# AiwacA33.net
KiCad netlist of a schematic drawn in Altium Designer
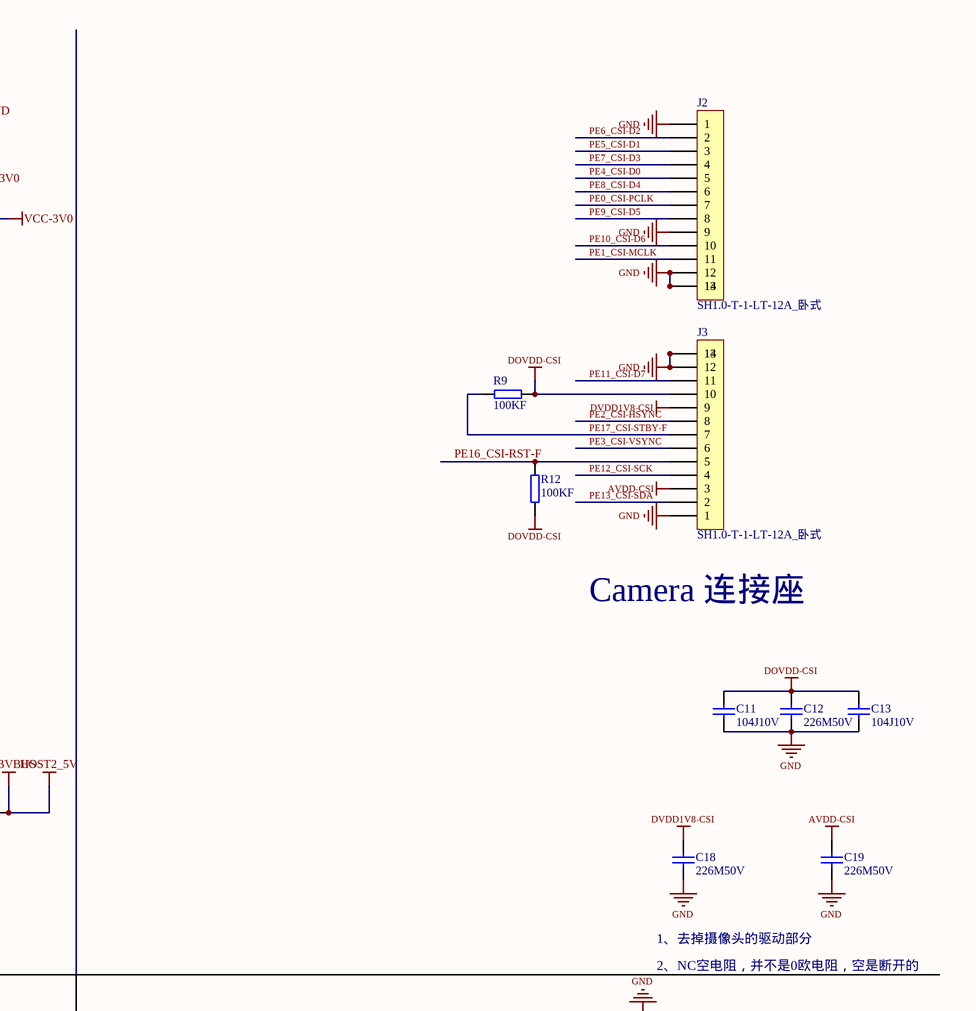
[diagram p0: AiwacA33.SchDoc, top right]
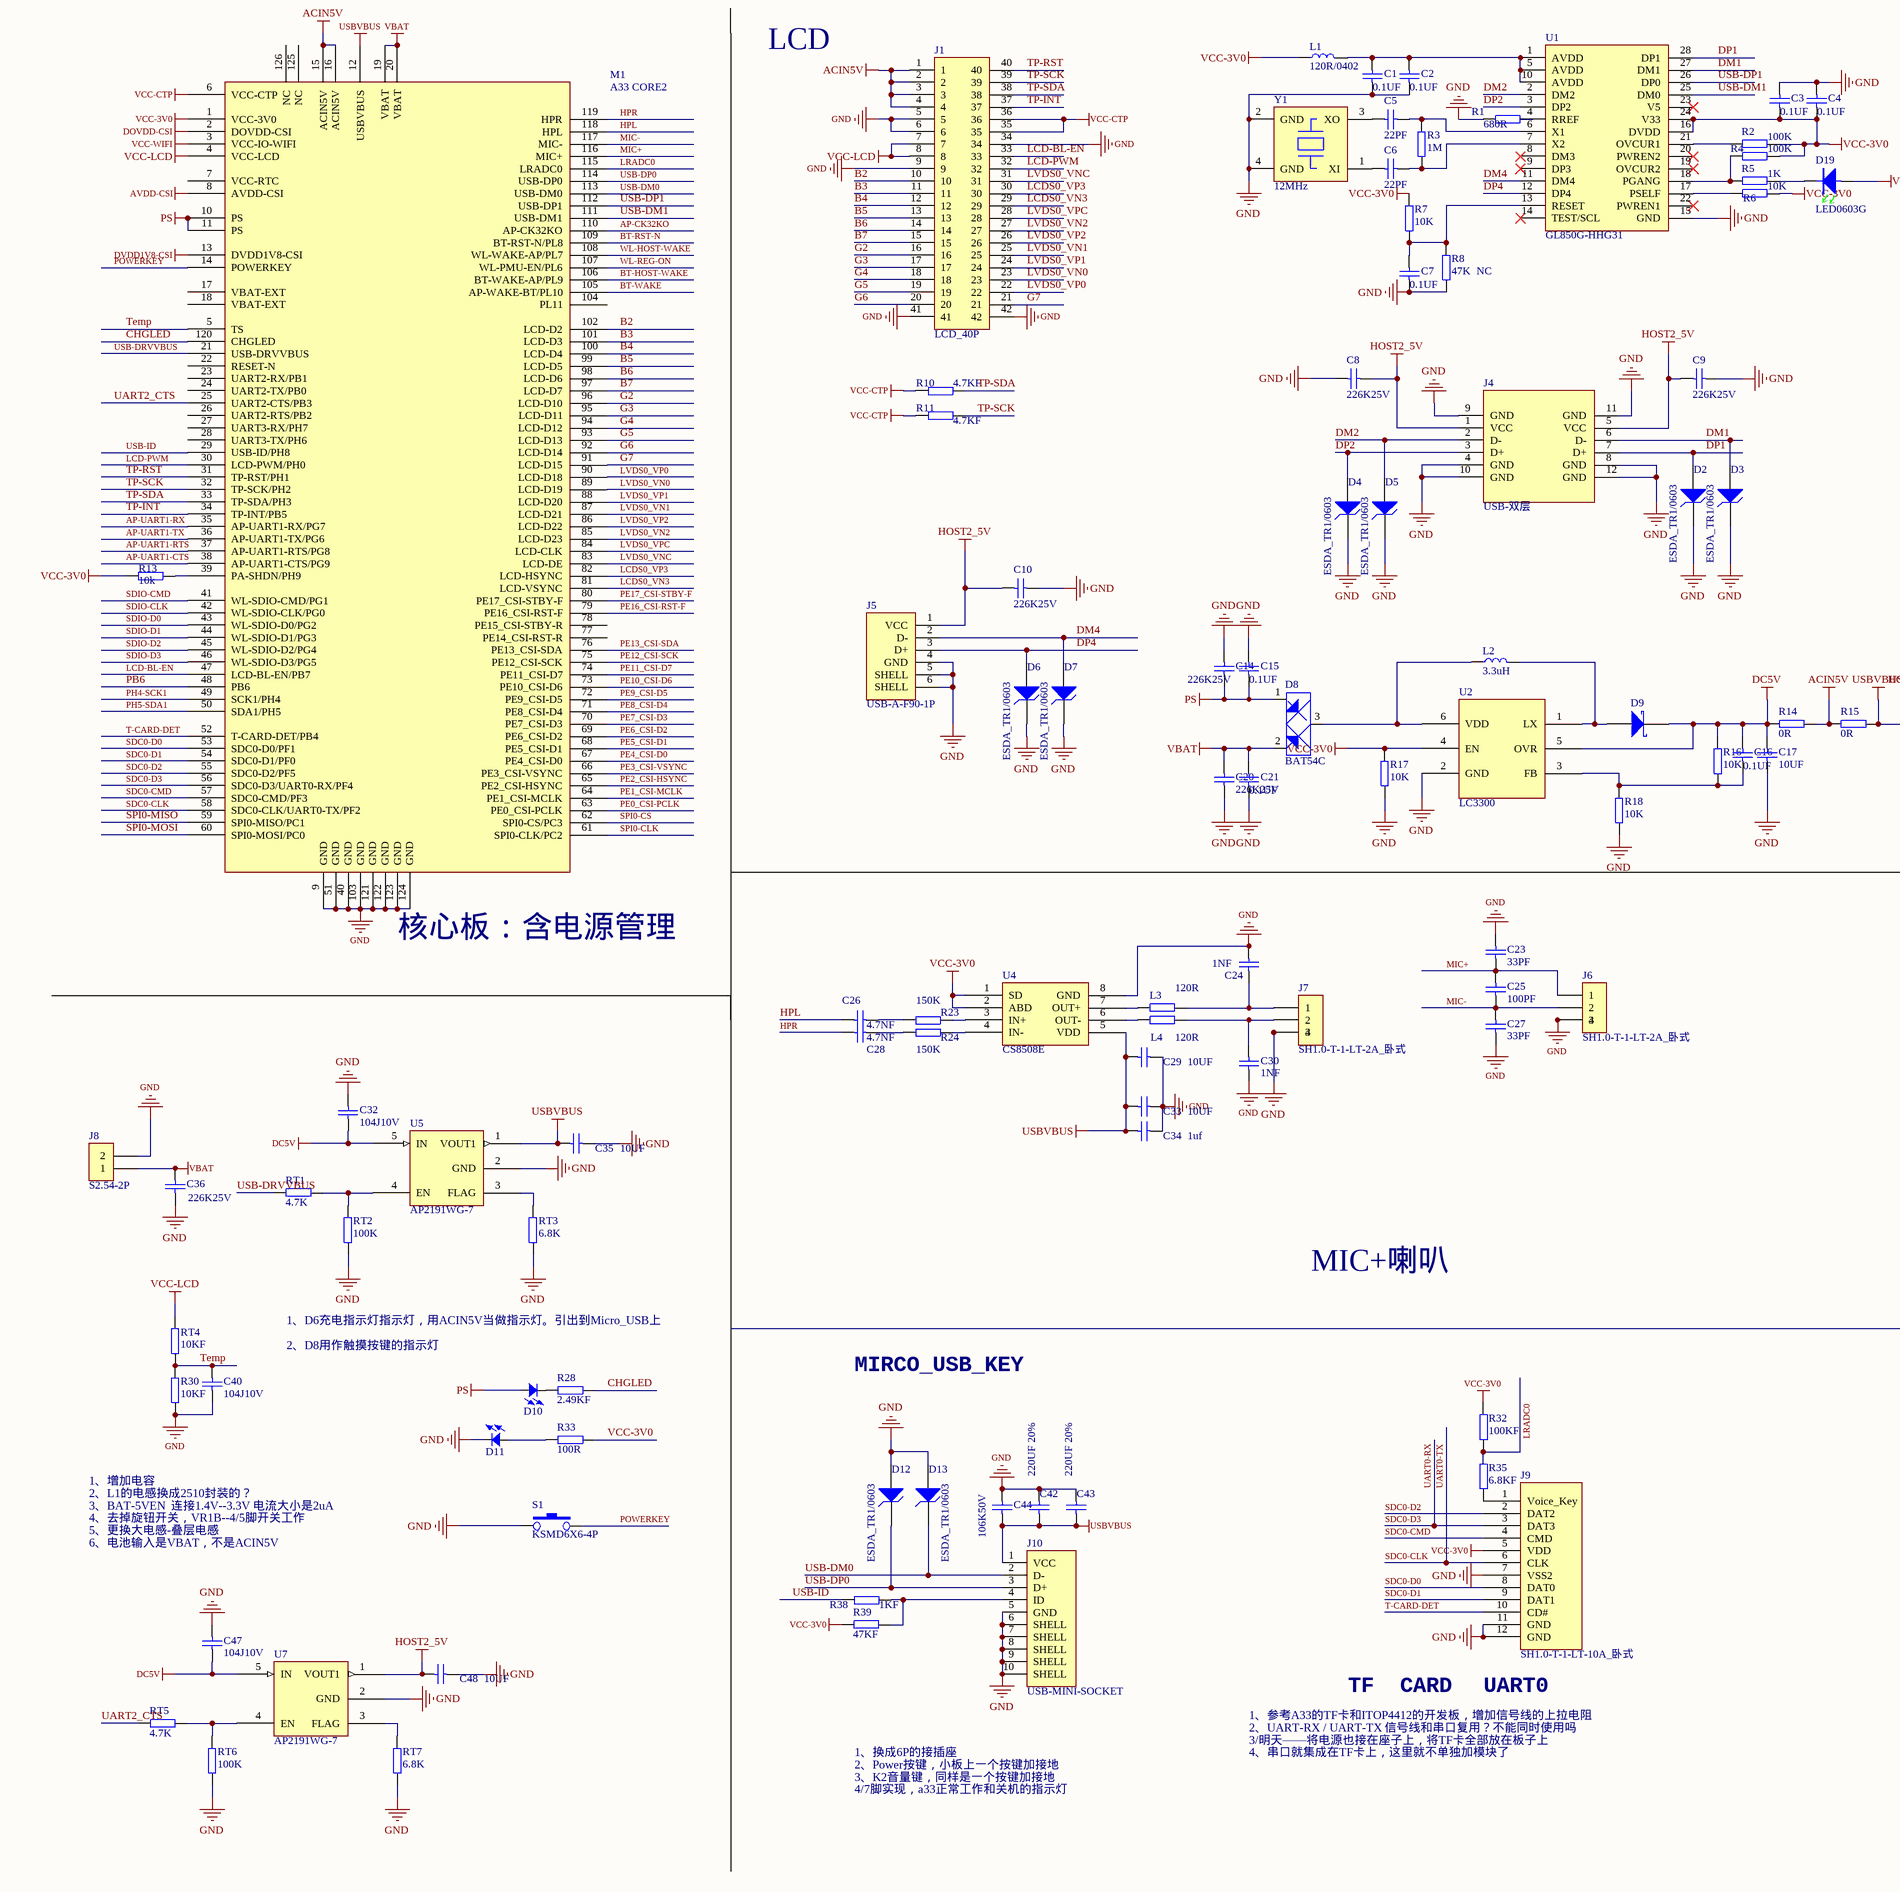
[diagram p1: AiwacA33.SchDoc, bottom left]
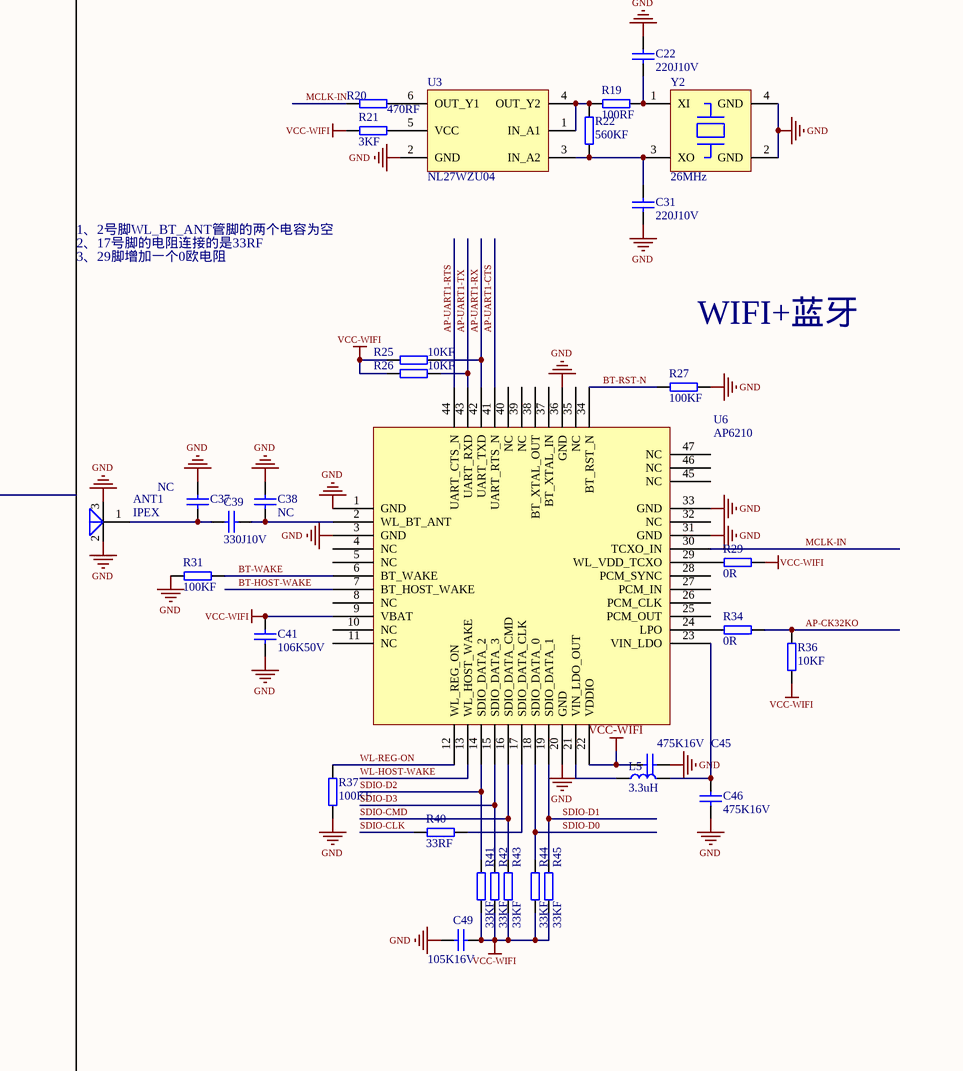
[diagram p2: AiwacA33.SchDoc, bottom right]

(export (version "E")
  (design (tool "Eeschema 10.0.6"))
  (components
    (comp (ref "ANT1")
      (value "IPEX")
      (footprint "J-IPEX")
      (description "天线接口IPEX")
      (libsource (lib "Connector") (part "J-IPEX"))
    )
    (comp (ref "C1")
      (value "0.1UF")
      (footprint "C0402")
      (description "贴片电容-陶瓷")
      (libsource (lib "AIWAC-bolsterV01") (part "C0402X7R-101J10V"))
    )
    (comp (ref "C2")
      (value "0.1UF")
      (footprint "C0402")
      (description "贴片电容-陶瓷")
      (libsource (lib "AIWAC-bolsterV01") (part "C0402X7R-101J10V"))
    )
    (comp (ref "C3")
      (value "0.1UF")
      (footprint "C0402")
      (description "贴片电容-陶瓷")
      (libsource (lib "AIWAC-bolsterV01") (part "C0402X7R-101J10V"))
    )
    (comp (ref "C4")
      (value "0.1UF")
      (footprint "C0402")
      (description "贴片电容-陶瓷")
      (libsource (lib "AIWAC-bolsterV01") (part "C0402X7R-101J10V"))
    )
    (comp (ref "C5")
      (value "22PF")
      (footprint "C0402")
      (description "贴片电容-陶瓷")
      (libsource (lib "AIWAC-bolsterV01") (part "C0402X7R-101J10V"))
    )
    (comp (ref "C6")
      (value "22PF")
      (footprint "C0402")
      (description "贴片电容-陶瓷")
      (libsource (lib "AIWAC-bolsterV01") (part "C0402X7R-101J10V"))
    )
    (comp (ref "C7")
      (value "0.1UF")
      (footprint "C0402")
      (description "贴片电容-陶瓷")
      (libsource (lib "AIWAC-bolsterV01") (part "C0402X7R-101J10V"))
    )
    (comp (ref "C8")
      (value "226K25V")
      (footprint "C0805")
      (description "贴片电容-陶瓷")
      (libsource (lib "Capacitor") (part "C0805X7R-226K25V"))
    )
    (comp (ref "C9")
      (value "226K25V")
      (footprint "C0805")
      (description "贴片电容-陶瓷")
      (libsource (lib "Capacitor") (part "C0805X7R-226K25V"))
    )
    (comp (ref "C10")
      (value "226K25V")
      (footprint "C0805")
      (description "贴片电容-陶瓷")
      (libsource (lib "Capacitor") (part "C0805X7R-226K25V"))
    )
    (comp (ref "C11")
      (value "104J10V")
      (footprint "C0402")
      (description "贴片电容-陶瓷")
      (libsource (lib "Capacitor") (part "C0402X7R-104J10V"))
    )
    (comp (ref "C12")
      (value "226M50V")
      (footprint "C0805")
      (description "贴片电容-陶瓷")
      (libsource (lib "Capacitor") (part "C0805Y5V-226M50V"))
    )
    (comp (ref "C13")
      (value "104J10V")
      (footprint "C0402")
      (description "贴片电容-陶瓷")
      (libsource (lib "Capacitor") (part "C0402X7R-104J10V"))
    )
    (comp (ref "C14")
      (value "226K25V")
      (footprint "C0805")
      (description "贴片电容-陶瓷")
      (libsource (lib "Capacitor") (part "C0805X7R-226K25V"))
    )
    (comp (ref "C15")
      (value "0.1UF")
      (footprint "C0402")
      (description "贴片电容-陶瓷")
      (libsource (lib "AIWAC-bolsterV01") (part "C0402X7R-101J10V"))
    )
    (comp (ref "C16")
      (value "0.1UF")
      (footprint "C0402")
      (description "贴片电容-陶瓷")
      (libsource (lib "AIWAC-bolsterV01") (part "C0402X7R-101J10V"))
    )
    (comp (ref "C17")
      (value "10UF")
      (footprint "C0603")
      (description "贴片电容-陶瓷")
      (libsource (lib "Capacitor") (part "C0603X7R-330J25V"))
    )
    (comp (ref "C18")
      (value "226M50V")
      (footprint "C0805")
      (description "贴片电容-陶瓷")
      (libsource (lib "Capacitor") (part "C0805Y5V-226M50V"))
    )
    (comp (ref "C19")
      (value "226M50V")
      (footprint "C0805")
      (description "贴片电容-陶瓷")
      (libsource (lib "Capacitor") (part "C0805Y5V-226M50V"))
    )
    (comp (ref "C20")
      (value "226K25V")
      (footprint "C0805")
      (description "贴片电容-陶瓷")
      (libsource (lib "Capacitor") (part "C0805X7R-226K25V"))
    )
    (comp (ref "C21")
      (value "0.1UF")
      (footprint "C0402")
      (description "贴片电容-陶瓷")
      (libsource (lib "AIWAC-bolsterV01") (part "C0402X7R-101J10V"))
    )
    (comp (ref "C22")
      (value "220J10V")
      (footprint "C0402")
      (description "贴片电容-陶瓷")
      (libsource (lib "Capacitor") (part "C0402X7R-220J10V"))
    )
    (comp (ref "C23")
      (value "33PF")
      (footprint "C0402")
      (description "贴片电容-陶瓷")
      (libsource (lib "Capacitor") (part "C0402X7R-104J10V"))
    )
    (comp (ref "C24")
      (value "1NF")
      (footprint "C0402")
      (description "贴片电容-陶瓷")
      (libsource (lib "Capacitor") (part "C0402X7R-220J10V"))
    )
    (comp (ref "C25")
      (value "100PF")
      (footprint "C0402")
      (description "贴片电容-陶瓷")
      (libsource (lib "Capacitor") (part "C0402X7R-104J10V"))
    )
    (comp (ref "C26")
      (value "4.7NF")
      (footprint "C0603")
      (description "贴片电容-陶瓷")
      (libsource (lib "Capacitor") (part "C0603X7R-330J25V"))
    )
    (comp (ref "C27")
      (value "33PF")
      (footprint "C0402")
      (description "贴片电容-陶瓷")
      (libsource (lib "Capacitor") (part "C0402X7R-104J10V"))
    )
    (comp (ref "C28")
      (value "4.7NF")
      (footprint "C0603")
      (description "贴片电容-陶瓷")
      (libsource (lib "Capacitor") (part "C0603X7R-330J25V"))
    )
    (comp (ref "C29")
      (value "10UF")
      (footprint "C0603")
      (description "贴片电容-陶瓷")
      (libsource (lib "Capacitor") (part "C0603X7R-330J25V"))
    )
    (comp (ref "C30")
      (value "1NF")
      (footprint "C0402")
      (description "贴片电容-陶瓷")
      (libsource (lib "Capacitor") (part "C0402X7R-220J10V"))
    )
    (comp (ref "C31")
      (value "220J10V")
      (footprint "C0402")
      (description "贴片电容-陶瓷")
      (libsource (lib "Capacitor") (part "C0402X7R-220J10V"))
    )
    (comp (ref "C32")
      (value "104J10V")
      (footprint "C0402")
      (description "贴片电容-陶瓷")
      (libsource (lib "Capacitor") (part "C0402X7R-104J10V"))
    )
    (comp (ref "C33")
      (value "10UF")
      (footprint "C0603")
      (description "贴片电容-陶瓷")
      (libsource (lib "Capacitor") (part "C0603X7R-330J25V"))
    )
    (comp (ref "C34")
      (value "1uf")
      (footprint "C0603")
      (description "贴片电容-陶瓷")
      (libsource (lib "Capacitor") (part "C0603X7R-330J25V"))
    )
    (comp (ref "C35")
      (value "10UF")
      (footprint "C0603")
      (description "贴片电容-陶瓷")
      (libsource (lib "Capacitor") (part "C0603X7R-330J25V"))
    )
    (comp (ref "C36")
      (value "226K25V")
      (footprint "C0805")
      (description "贴片电容-陶瓷")
      (libsource (lib "Capacitor") (part "C0805X7R-226K25V"))
    )
    (comp (ref "C37")
      (value "NC")
      (footprint "C0402")
      (description "贴片电容-陶瓷")
      (libsource (lib "Capacitor") (part "C0402X7R-220J10V"))
    )
    (comp (ref "C38")
      (value "NC")
      (footprint "C0402")
      (description "贴片电容-陶瓷")
      (libsource (lib "Capacitor") (part "C0402X7R-220J10V"))
    )
    (comp (ref "C39")
      (value "330J10V")
      (footprint "C0402")
      (description "贴片电容-陶瓷")
      (libsource (lib "Capacitor") (part "C0402X7R-330J10V"))
    )
    (comp (ref "C40")
      (value "104J10V")
      (footprint "C0402")
      (description "贴片电容-陶瓷")
      (libsource (lib "Capacitor") (part "C0402X7R-104J10V"))
    )
    (comp (ref "C41")
      (value "106K50V")
      (footprint "C0603")
      (description "贴片电容-陶瓷")
      (libsource (lib "Capacitor") (part "C0603X7R-106K50V"))
    )
    (comp (ref "C42")
      (value "220UF 20%")
      (footprint "C1206")
      (description "C 1206钽电容 --220UF 10V 3216 A型 有极性电容 3.2mm X 1.6mm")
      (libsource (lib "Capacitor") (part "C1206-A型 极性电容"))
    )
    (comp (ref "C43")
      (value "220UF 20%")
      (footprint "C1206")
      (description "C 1206钽电容 --220UF 10V 3216 A型 有极性电容 3.2mm X 1.6mm")
      (libsource (lib "Capacitor") (part "C1206-A型 极性电容"))
    )
    (comp (ref "C44")
      (value "106K50V")
      (footprint "C0603")
      (description "贴片电容-陶瓷")
      (libsource (lib "Capacitor") (part "C0603X7R-106K50V"))
    )
    (comp (ref "C45")
      (value "475K16V")
      (footprint "C0603")
      (description "贴片电容-陶瓷")
      (libsource (lib "Capacitor") (part "C0603X7R-475K16V"))
    )
    (comp (ref "C46")
      (value "475K16V")
      (footprint "C0603")
      (description "贴片电容-陶瓷")
      (libsource (lib "Capacitor") (part "C0603X7R-475K16V"))
    )
    (comp (ref "C47")
      (value "104J10V")
      (footprint "C0402")
      (description "贴片电容-陶瓷")
      (libsource (lib "Capacitor") (part "C0402X7R-104J10V"))
    )
    (comp (ref "C48")
      (value "10UF")
      (footprint "C0603")
      (description "贴片电容-陶瓷")
      (libsource (lib "Capacitor") (part "C0603X7R-330J25V"))
    )
    (comp (ref "C49")
      (value "105K16V")
      (footprint "C0603")
      (description "贴片电容-陶瓷")
      (libsource (lib "Capacitor") (part "C0603X7R-105K16V"))
    )
    (comp (ref "D2")
      (value "ESDA_TR1/0603")
      (footprint "HS_0603D")
      (description "Zener Diode")
      (fields (field (name "PUBLISHER") "*"))
      (libsource (lib "1_1") (part "D Zener"))
    )
    (comp (ref "D3")
      (value "ESDA_TR1/0603")
      (footprint "HS_0603D")
      (description "Zener Diode")
      (fields (field (name "PUBLISHER") "*"))
      (libsource (lib "1_1") (part "D Zener"))
    )
    (comp (ref "D4")
      (value "ESDA_TR1/0603")
      (footprint "HS_0603D")
      (description "Zener Diode")
      (fields (field (name "PUBLISHER") "*"))
      (libsource (lib "1_1") (part "D Zener"))
    )
    (comp (ref "D5")
      (value "ESDA_TR1/0603")
      (footprint "HS_0603D")
      (description "Zener Diode")
      (fields (field (name "PUBLISHER") "*"))
      (libsource (lib "1_1") (part "D Zener"))
    )
    (comp (ref "D6")
      (value "ESDA_TR1/0603")
      (footprint "HS_0603D")
      (description "Zener Diode")
      (fields (field (name "PUBLISHER") "*"))
      (libsource (lib "1_1") (part "D Zener"))
    )
    (comp (ref "D7")
      (value "ESDA_TR1/0603")
      (footprint "HS_0603D")
      (description "Zener Diode")
      (fields (field (name "PUBLISHER") "*"))
      (libsource (lib "1_1") (part "D Zener"))
    )
    (comp (ref "D8")
      (value "BAT54C")
      (footprint "SOT23-BAT54C")
      (libsource (lib "AIWAC-bolsterV01") (part "BAT54C"))
    )
    (comp (ref "D9")
      (value "D Schottky")
      (footprint "SMB")
      (description "Schottky Diode")
      (fields (field (name "PUBLISHER") "Altium Limited"))
      (libsource (lib "XU-GENARAL SCH") (part "D Schottky"))
    )
    (comp (ref "D10")
      (value "发光二极管")
      (footprint "AIWAC_20181112:LEDΦ5-H12")
      (libsource (lib "1_1") (part "发光二极管"))
    )
    (comp (ref "D11")
      (value "发光二极管")
      (footprint "AIWAC_20181112:LEDΦ5-H12")
      (libsource (lib "1_1") (part "发光二极管"))
    )
    (comp (ref "D12")
      (value "ESDA_TR1/0603")
      (footprint "HS_0603D")
      (description "Zener Diode")
      (fields (field (name "PUBLISHER") "*"))
      (libsource (lib "1_1") (part "D Zener"))
    )
    (comp (ref "D13")
      (value "ESDA_TR1/0603")
      (footprint "HS_0603D")
      (description "Zener Diode")
      (fields (field (name "PUBLISHER") "*"))
      (libsource (lib "1_1") (part "D Zener"))
    )
    (comp (ref "D19")
      (value "LED0603G")
      (footprint "D-LED0603G")
      (description "贴片二极管-LED")
      (libsource (lib "AIWAC-bolsterV01") (part "DLED-0603-G"))
    )
    (comp (ref "J1") (value "LCD_40P") (footprint "LCD P40") (libsource (lib "Connector") (part "LCD_40P")))
    (comp (ref "J2")
      (value "SH1.0-T-1-LT-12A_卧式")
      (footprint "J-SH1.0-T-1-LT-12A_卧式")
      (libsource (lib "") (part "SH1.0-T-1-LT-12A_卧式_1"))
    )
    (comp (ref "J3")
      (value "SH1.0-T-1-LT-12A_卧式")
      (footprint "J-SH1.0-T-1-LT-12A_卧式")
      (libsource (lib "Connector") (part "SH1.0-T-1-LT-12A_卧式"))
    )
    (comp (ref "J4")
      (value "USB-双层")
      (footprint "USB-双层卧式")
      (description "USB-B卧式插座")
      (libsource (lib "Sheye-Connector") (part "J-USB-双层卧式"))
    )
    (comp (ref "J5")
      (value "USB-A-F90-1P")
      (footprint "USB-A-F90-侧卧")
      (description "USB-A卧式插座")
      (libsource (lib "Sheye-Connector") (part "J-USB-A-F90-1P"))
    )
    (comp (ref "J6")
      (value "SH1.0-T-1-LT-2A_卧式")
      (footprint "J-SH1.0-T-1-LT-2A_卧式")
      (libsource (lib "Connector") (part "SH1.0-T-1-LT-2A_卧式"))
    )
    (comp (ref "J7")
      (value "SH1.0-T-1-LT-2A_卧式")
      (footprint "J-SH1.0-T-1-LT-2A_卧式")
      (libsource (lib "Connector") (part "SH1.0-T-1-LT-2A_卧式"))
    )
    (comp (ref "J8")
      (value "S2.54-2P")
      (footprint "S2.54-2P")
      (description "单排排针-直针")
      (libsource (lib "Sheye-Connector") (part "J-S2.54-2P"))
    )
    (comp (ref "J9")
      (value "SH1.0-T-1-LT-10A_卧式")
      (footprint "J-SH1.0-T-1-LT-10A_卧式")
      (libsource (lib "Connector") (part "SH1.0-T-1-LT-10A_卧式"))
    )
    (comp (ref "J10")
      (value "USB-MINI-SOCKET")
      (footprint "MICRO-USB - 5.9")
      (description "USB-A卧式插座")
      (libsource (lib "Connector") (part "J-USB-MINI-SOCKET"))
    )
    (comp (ref "L1")
      (value "120R/0402")
      (footprint "C0402")
      (description "贴片电感-屏蔽")
      (libsource (lib "AIWAC-bolsterV01") (part "3.3uH"))
    )
    (comp (ref "L2")
      (value "3.3uH")
      (footprint "D1206")
      (description "贴片电感-屏蔽")
      (libsource (lib "AIWAC-bolsterV01") (part "3.3uH"))
    )
    (comp (ref "L3")
      (value "120R")
      (footprint "R0603")
      (description "贴片电阻-通用")
      (libsource (lib "Resistor") (part "R0603-47KF"))
    )
    (comp (ref "L4")
      (value "120R")
      (footprint "R0603")
      (description "贴片电阻-通用")
      (libsource (lib "Resistor") (part "R0603-47KF"))
    )
    (comp (ref "L5")
      (value "3.3uH")
      (footprint "L0805")
      (description "贴片电感-层叠")
      (libsource (lib "magnetic") (part "L-0805-3.3uH"))
    )
    (comp (ref "M1")
      (value "A33 CORE2")
      (footprint "AIWAC_20181112:A33-CORE2")
      (libsource (lib "Module") (part "A33 CORE2"))
    )
    (comp (ref "R1")
      (value "680R")
      (footprint "R0402")
      (description "贴片电阻-通用")
      (libsource (lib "AIWAC-bolsterV01") (part "R0402-1KF"))
    )
    (comp (ref "R2")
      (value "100K")
      (footprint "R0402")
      (description "贴片电阻-通用")
      (libsource (lib "AIWAC-bolsterV01") (part "R0402-1KF"))
    )
    (comp (ref "R3")
      (value "1M")
      (footprint "R0402")
      (description "贴片电阻-通用")
      (libsource (lib "AIWAC-bolsterV01") (part "R0402-1KF"))
    )
    (comp (ref "R4")
      (value "100K")
      (footprint "R0402")
      (description "贴片电阻-通用")
      (libsource (lib "AIWAC-bolsterV01") (part "R0402-1KF"))
    )
    (comp (ref "R5")
      (value "1K")
      (footprint "R0402")
      (description "贴片电阻-通用")
      (libsource (lib "AIWAC-bolsterV01") (part "R0402-1KF"))
    )
    (comp (ref "R6")
      (value "10K")
      (footprint "R0402")
      (description "贴片电阻-通用")
      (libsource (lib "AIWAC-bolsterV01") (part "R0402-1KF"))
    )
    (comp (ref "R7")
      (value "10K")
      (footprint "R0402")
      (description "贴片电阻-通用")
      (libsource (lib "AIWAC-bolsterV01") (part "R0402-1KF"))
    )
    (comp (ref "R8")
      (value "47K  NC")
      (footprint "R0402")
      (description "贴片电阻-通用")
      (libsource (lib "AIWAC-bolsterV01") (part "R0402-1KF"))
    )
    (comp (ref "R9")
      (value "100KF")
      (footprint "R0603")
      (description "贴片电阻-通用")
      (libsource (lib "Resistor") (part "R0603-100KF"))
    )
    (comp (ref "R10")
      (value "4.7KF")
      (footprint "R0402")
      (description "贴片电阻-通用")
      (libsource (lib "Resistor") (part "R0402-4.7KF"))
    )
    (comp (ref "R11")
      (value "4.7KF")
      (footprint "R0402")
      (description "贴片电阻-通用")
      (libsource (lib "Resistor") (part "R0402-4.7KF"))
    )
    (comp (ref "R12")
      (value "100KF")
      (footprint "R0603")
      (description "贴片电阻-通用")
      (libsource (lib "Resistor") (part "R0603-100KF"))
    )
    (comp (ref "R13")
      (value "10k")
      (footprint "R0603")
      (description "贴片电阻-通用")
      (libsource (lib "Resistor") (part "R0603-10KF"))
    )
    (comp (ref "R14")
      (value "0R")
      (footprint "R0603")
      (description "贴片电阻-通用")
      (libsource (lib "Resistor") (part "R0603-2KF"))
    )
    (comp (ref "R15")
      (value "0R")
      (footprint "R0603")
      (description "贴片电阻-通用")
      (libsource (lib "Resistor") (part "R0603-2KF"))
    )
    (comp (ref "R16")
      (value "10K")
      (footprint "R0603")
      (description "贴片电阻-通用")
      (libsource (lib "Resistor") (part "R0603-2KF"))
    )
    (comp (ref "R17")
      (value "10K")
      (footprint "R0603")
      (description "贴片电阻-通用")
      (libsource (lib "Resistor") (part "R0603-2KF"))
    )
    (comp (ref "R18")
      (value "10K")
      (footprint "R0603")
      (description "贴片电阻-通用")
      (libsource (lib "Resistor") (part "R0603-2KF"))
    )
    (comp (ref "R19")
      (value "100RF")
      (footprint "R0603")
      (description "贴片电阻-通用")
      (libsource (lib "Resistor") (part "R0603-100RF"))
    )
    (comp (ref "R20")
      (value "470RF")
      (footprint "R0603")
      (description "贴片电阻-通用")
      (libsource (lib "Resistor") (part "R0603-470RF"))
    )
    (comp (ref "R21")
      (value "3KF")
      (footprint "R0603")
      (description "贴片电阻-通用")
      (libsource (lib "Resistor") (part "R0603-3KF"))
    )
    (comp (ref "R22")
      (value "560KF")
      (footprint "R0603")
      (description "贴片电阻-通用")
      (libsource (lib "Resistor") (part "R0603-560KF"))
    )
    (comp (ref "R23")
      (value "150K")
      (footprint "R0603")
      (description "贴片电阻-通用")
      (libsource (lib "Resistor") (part "R0603-10KF"))
    )
    (comp (ref "R24")
      (value "150K")
      (footprint "R0603")
      (description "贴片电阻-通用")
      (libsource (lib "Resistor") (part "R0603-10KF"))
    )
    (comp (ref "R25")
      (value "10KF")
      (footprint "R0603")
      (description "贴片电阻-通用")
      (libsource (lib "Resistor") (part "R0603-10KF"))
    )
    (comp (ref "R26")
      (value "10KF")
      (footprint "R0603")
      (description "贴片电阻-通用")
      (libsource (lib "Resistor") (part "R0603-10KF"))
    )
    (comp (ref "R27")
      (value "100KF")
      (footprint "R0603")
      (description "贴片电阻-通用")
      (libsource (lib "Resistor") (part "R0603-100KF"))
    )
    (comp (ref "R28")
      (value "2.49KF")
      (footprint "R0603")
      (description "贴片电阻-通用")
      (libsource (lib "Resistor") (part "R0603-3KF"))
    )
    (comp (ref "R29")
      (value "0R")
      (footprint "R0603")
      (description "贴片电阻-通用")
      (libsource (lib "Resistor") (part "R0603-0R"))
    )
    (comp (ref "R30")
      (value "10KF")
      (footprint "R0603")
      (description "贴片电阻-通用")
      (libsource (lib "Resistor") (part "R0603-10KF"))
    )
    (comp (ref "R31")
      (value "100KF")
      (footprint "R0603")
      (description "贴片电阻-通用")
      (libsource (lib "Resistor") (part "R0603-100KF"))
    )
    (comp (ref "R32")
      (value "100KF")
      (footprint "R0603")
      (description "贴片电阻-通用")
      (libsource (lib "Resistor") (part "R0603-100KF"))
    )
    (comp (ref "R33")
      (value "100R")
      (footprint "R0603")
      (description "贴片电阻-通用")
      (libsource (lib "Resistor") (part "R0603-2KF"))
    )
    (comp (ref "R34")
      (value "0R")
      (footprint "R0603")
      (description "贴片电阻-通用")
      (libsource (lib "Resistor") (part "R0603-0R"))
    )
    (comp (ref "R35")
      (value "6.8KF")
      (footprint "R0603")
      (description "贴片电阻-通用")
      (libsource (lib "Resistor") (part "R0603-6.8KF"))
    )
    (comp (ref "R36")
      (value "10KF")
      (footprint "R0603")
      (description "贴片电阻-通用")
      (libsource (lib "Resistor") (part "R0603-10KF"))
    )
    (comp (ref "R37")
      (value "100KF")
      (footprint "R0603")
      (description "贴片电阻-通用")
      (libsource (lib "Resistor") (part "R0603-100KF"))
    )
    (comp (ref "R38")
      (value "1KF")
      (footprint "R0603")
      (description "贴片电阻-通用")
      (libsource (lib "Resistor") (part "R0603-1KF"))
    )
    (comp (ref "R39")
      (value "47KF")
      (footprint "R0603")
      (description "贴片电阻-通用")
      (libsource (lib "Resistor") (part "R0603-47KF"))
    )
    (comp (ref "R40")
      (value "33RF")
      (footprint "R0603")
      (description "贴片电阻-通用")
      (libsource (lib "Resistor") (part "R0603-33RF"))
    )
    (comp (ref "R41")
      (value "33KF")
      (footprint "R0603")
      (description "贴片电阻-通用")
      (libsource (lib "Resistor") (part "R0603-33KF"))
    )
    (comp (ref "R42")
      (value "33KF")
      (footprint "R0603")
      (description "贴片电阻-通用")
      (libsource (lib "Resistor") (part "R0603-33KF"))
    )
    (comp (ref "R43")
      (value "33KF")
      (footprint "R0603")
      (description "贴片电阻-通用")
      (libsource (lib "Resistor") (part "R0603-33KF"))
    )
    (comp (ref "R44")
      (value "33KF")
      (footprint "R0603")
      (description "贴片电阻-通用")
      (libsource (lib "Resistor") (part "R0603-33KF"))
    )
    (comp (ref "R45")
      (value "33KF")
      (footprint "R0603")
      (description "贴片电阻-通用")
      (libsource (lib "Resistor") (part "R0603-33KF"))
    )
    (comp (ref "RT1")
      (value "4.7K")
      (footprint "XU-GENARAL PCB :0402")
      (description "贴片电阻-通用")
      (libsource (lib "Resistor") (part "R0603-10KF"))
    )
    (comp (ref "RT2")
      (value "100K")
      (footprint "XU-GENARAL PCB :0402")
      (description "贴片电阻-通用")
      (libsource (lib "Resistor") (part "R0603-10KF"))
    )
    (comp (ref "RT3")
      (value "6.8K")
      (footprint "XU-GENARAL PCB :0402")
      (description "贴片电阻-通用")
      (libsource (lib "Resistor") (part "R0603-10KF"))
    )
    (comp (ref "RT4")
      (value "10KF")
      (footprint "XU-GENARAL PCB :0402")
      (description "贴片电阻-通用")
      (libsource (lib "Resistor") (part "R0603-10KF"))
    )
    (comp (ref "RT5")
      (value "4.7K")
      (footprint "XU-GENARAL PCB :0402")
      (description "贴片电阻-通用")
      (libsource (lib "Resistor") (part "R0603-10KF"))
    )
    (comp (ref "RT6")
      (value "100K")
      (footprint "XU-GENARAL PCB :0402")
      (description "贴片电阻-通用")
      (libsource (lib "Resistor") (part "R0603-10KF"))
    )
    (comp (ref "RT7")
      (value "6.8K")
      (footprint "XU-GENARAL PCB :0402")
      (description "贴片电阻-通用")
      (libsource (lib "Resistor") (part "R0603-10KF"))
    )
    (comp (ref "S1")
      (value "KSMD6X6-4P")
      (footprint "AIWAC_20181112:SW2-6*6H")
      (description "轻触按键")
      (libsource (lib "Key") (part "S-KSMD6X6-4P"))
    )
    (comp (ref "U1")
      (value "GL850G-HHG31")
      (footprint "SSOP28")
      (libsource (lib "AIWAC-bolsterV01") (part "GL850G-HHG31"))
    )
    (comp (ref "U2")
      (value "LC3300")
      (footprint "SOT23-6")
      (libsource (lib "AIWAC-bolsterV01") (part "LC3300"))
    )
    (comp (ref "U3") (value "NL27WZU04") (footprint "U-TSOP-6") (libsource (lib "IC") (part "NL27WZU04")))
    (comp (ref "U4") (value "CS8508E") (footprint "SO-8") (libsource (lib "PCB_Project_1") (part "CS8508E")))
    (comp (ref "U5")
      (value "AP2191WG-7")
      (footprint "SOT23-5")
      (libsource (lib "AIWAC-bolsterV01") (part "AP2191WG-7"))
    )
    (comp (ref "U6")
      (value "AP6210")
      (footprint "AIWAC-bolsterV01:AP6210")
      (libsource (lib "IC") (part "AP6210"))
    )
    (comp (ref "U7")
      (value "AP2191WG-7")
      (footprint "SOT23-5")
      (libsource (lib "AIWAC-bolsterV01") (part "AP2191WG-7"))
    )
    (comp (ref "Y1")
      (value "12MHz")
      (footprint "AIWAC-bolsterV01:Y-CPX-32GA-4P")
      (description "晶振-贴片无源")
      (libsource (lib "AIWAC-bolsterV01") (part "YC-26MHz"))
    )
    (comp (ref "Y2")
      (value "26MHz")
      (footprint "Y-CPX-32GA-4P")
      (description "晶振-贴片无源")
      (libsource (lib "Others") (part "YC-26MHz"))
    )
  )
  (nets
    (net (code "1") (name "/AP-CK32KO") (class "Default")
      (node (ref "M1") (pin "110") (pinfunction "AP-CK32KO_110") (pintype "passive"))
      (node (ref "R34") (pin "2") (pinfunction "2_2") (pintype "passive"))
      (node (ref "R36") (pin "2") (pinfunction "2_2") (pintype "passive"))
    )
    (net (code "2") (name "/AP-UART1-CTS") (class "Default")
      (node (ref "M1") (pin "38") (pinfunction "AP-UART1-CTS/PG9_38") (pintype "passive"))
      (node (ref "U6") (pin "41") (pinfunction "UART_RTS_N_41") (pintype "passive"))
    )
    (net (code "3") (name "/AP-UART1-RTS") (class "Default")
      (node (ref "M1") (pin "37") (pinfunction "AP-UART1-RTS/PG8_37") (pintype "passive"))
      (node (ref "U6") (pin "44") (pinfunction "UART_CTS_N_44") (pintype "passive"))
    )
    (net (code "4") (name "/AP-UART1-RX") (class "Default")
      (node (ref "M1") (pin "35") (pinfunction "AP-UART1-RX/PG7_35") (pintype "passive"))
      (node (ref "R25") (pin "2") (pinfunction "2_2") (pintype "passive"))
      (node (ref "U6") (pin "42") (pinfunction "UART_TXD_42") (pintype "passive"))
    )
    (net (code "5") (name "/AP-UART1-TX") (class "Default")
      (node (ref "M1") (pin "36") (pinfunction "AP-UART1-TX/PG6_36") (pintype "passive"))
      (node (ref "R26") (pin "2") (pinfunction "2_2") (pintype "passive"))
      (node (ref "U6") (pin "43") (pinfunction "UART_RXD_43") (pintype "passive"))
    )
    (net (code "6") (name "/B2") (class "Default")
      (node (ref "J1") (pin "10") (pinfunction "10_10") (pintype "passive"))
      (node (ref "M1") (pin "102") (pinfunction "LCD-D2_102") (pintype "passive"))
    )
    (net (code "7") (name "/B3") (class "Default")
      (node (ref "J1") (pin "11") (pinfunction "11_11") (pintype "passive"))
      (node (ref "M1") (pin "101") (pinfunction "LCD-D3_101") (pintype "passive"))
    )
    (net (code "8") (name "/B4") (class "Default")
      (node (ref "J1") (pin "12") (pinfunction "12_12") (pintype "passive"))
      (node (ref "M1") (pin "100") (pinfunction "LCD-D4_100") (pintype "passive"))
    )
    (net (code "9") (name "/B5") (class "Default")
      (node (ref "J1") (pin "13") (pinfunction "13_13") (pintype "passive"))
      (node (ref "M1") (pin "99") (pinfunction "LCD-D5_99") (pintype "passive"))
    )
    (net (code "10") (name "/B6") (class "Default")
      (node (ref "J1") (pin "14") (pinfunction "14_14") (pintype "passive"))
      (node (ref "M1") (pin "98") (pinfunction "LCD-D6_98") (pintype "passive"))
    )
    (net (code "11") (name "/B7") (class "Default")
      (node (ref "J1") (pin "15") (pinfunction "15_15") (pintype "passive"))
      (node (ref "M1") (pin "97") (pinfunction "LCD-D7_97") (pintype "passive"))
    )
    (net (code "12") (name "/BT-HOST-WAKE") (class "Default")
      (node (ref "M1") (pin "106") (pinfunction "BT-WAKE-AP/PL9_106") (pintype "passive"))
      (node (ref "U6") (pin "7") (pinfunction "BT_HOST_WAKE_7") (pintype "passive"))
    )
    (net (code "13") (name "/BT-RST-N") (class "Default")
      (node (ref "M1") (pin "109") (pinfunction "BT-RST-N/PL8_109") (pintype "passive"))
      (node (ref "R27") (pin "1") (pinfunction "1_1") (pintype "passive"))
      (node (ref "U6") (pin "34") (pinfunction "BT_RST_N_34") (pintype "passive"))
    )
    (net (code "14") (name "/BT-WAKE") (class "Default")
      (node (ref "M1") (pin "105") (pinfunction "AP-WAKE-BT/PL10_105") (pintype "passive"))
      (node (ref "R31") (pin "1") (pinfunction "1_1") (pintype "passive"))
      (node (ref "U6") (pin "6") (pinfunction "BT_WAKE_6") (pintype "passive"))
    )
    (net (code "15") (name "/CHGLED") (class "Default")
      (node (ref "M1") (pin "120") (pinfunction "CHGLED_120") (pintype "passive"))
      (node (ref "R28") (pin "2") (pinfunction "2_2") (pintype "passive"))
    )
    (net (code "16") (name "/DM1") (class "Default")
      (node (ref "D3") (pin "1") (pinfunction "A_1") (pintype "passive"))
      (node (ref "J4") (pin "6") (pinfunction "D-_6") (pintype "passive"))
      (node (ref "U1") (pin "27") (pinfunction "DM1_27") (pintype "passive"))
    )
    (net (code "17") (name "/DM2") (class "Default")
      (node (ref "D5") (pin "1") (pinfunction "A_1") (pintype "passive"))
      (node (ref "J4") (pin "2") (pinfunction "D-_2") (pintype "passive"))
      (node (ref "U1") (pin "2") (pinfunction "DM2_2") (pintype "passive"))
    )
    (net (code "18") (name "/DM4") (class "Default")
      (node (ref "D7") (pin "1") (pinfunction "A_1") (pintype "passive"))
      (node (ref "J5") (pin "2") (pinfunction "D-_2") (pintype "passive"))
      (node (ref "U1") (pin "11") (pinfunction "DM4_11") (pintype "passive"))
    )
    (net (code "19") (name "/DP1") (class "Default")
      (node (ref "D2") (pin "1") (pinfunction "A_1") (pintype "passive"))
      (node (ref "J4") (pin "7") (pinfunction "D+_7") (pintype "passive"))
      (node (ref "U1") (pin "28") (pinfunction "DP1_28") (pintype "passive"))
    )
    (net (code "20") (name "/DP2") (class "Default")
      (node (ref "D4") (pin "1") (pinfunction "A_1") (pintype "passive"))
      (node (ref "J4") (pin "3") (pinfunction "D+_3") (pintype "passive"))
      (node (ref "U1") (pin "3") (pinfunction "DP2_3") (pintype "passive"))
    )
    (net (code "21") (name "/DP4") (class "Default")
      (node (ref "D6") (pin "1") (pinfunction "A_1") (pintype "passive"))
      (node (ref "J5") (pin "3") (pinfunction "D+_3") (pintype "passive"))
      (node (ref "U1") (pin "12") (pinfunction "DP4_12") (pintype "passive"))
    )
    (net (code "22") (name "/G2") (class "Default")
      (node (ref "J1") (pin "16") (pinfunction "16_16") (pintype "passive"))
      (node (ref "M1") (pin "96") (pinfunction "LCD-D10_96") (pintype "passive"))
    )
    (net (code "23") (name "/G3") (class "Default")
      (node (ref "J1") (pin "17") (pinfunction "17_17") (pintype "passive"))
      (node (ref "M1") (pin "95") (pinfunction "LCD-D11_95") (pintype "passive"))
    )
    (net (code "24") (name "/G4") (class "Default")
      (node (ref "J1") (pin "18") (pinfunction "18_18") (pintype "passive"))
      (node (ref "M1") (pin "94") (pinfunction "LCD-D12_94") (pintype "passive"))
    )
    (net (code "25") (name "/G5") (class "Default")
      (node (ref "J1") (pin "19") (pinfunction "19_19") (pintype "passive"))
      (node (ref "M1") (pin "93") (pinfunction "LCD-D13_93") (pintype "passive"))
    )
    (net (code "26") (name "/G6") (class "Default")
      (node (ref "J1") (pin "20") (pinfunction "20_20") (pintype "passive"))
      (node (ref "M1") (pin "92") (pinfunction "LCD-D14_92") (pintype "passive"))
    )
    (net (code "27") (name "/G7") (class "Default")
      (node (ref "J1") (pin "21") (pinfunction "21_21") (pintype "passive"))
      (node (ref "M1") (pin "91") (pinfunction "LCD-D15_91") (pintype "passive"))
    )
    (net (code "28") (name "/HPL") (class "Default")
      (node (ref "C26") (pin "1") (pinfunction "1_1") (pintype "passive"))
      (node (ref "M1") (pin "118") (pinfunction "HPL_118") (pintype "passive"))
    )
    (net (code "29") (name "/HPR") (class "Default")
      (node (ref "C28") (pin "1") (pinfunction "1_1") (pintype "passive"))
      (node (ref "M1") (pin "119") (pinfunction "HPR_119") (pintype "passive"))
    )
    (net (code "30") (name "/LCD-BL-EN") (class "Default")
      (node (ref "J1") (pin "33") (pinfunction "33_33") (pintype "passive"))
      (node (ref "M1") (pin "47") (pinfunction "LCD-BL-EN/PB7_47") (pintype "passive"))
    )
    (net (code "31") (name "/LCD-PWM") (class "Default")
      (node (ref "J1") (pin "32") (pinfunction "32_32") (pintype "passive"))
      (node (ref "M1") (pin "30") (pinfunction "LCD-PWM/PH0_30") (pintype "passive"))
    )
    (net (code "32") (name "/LCDS0_VN3") (class "Default")
      (node (ref "J1") (pin "29") (pinfunction "29_29") (pintype "passive"))
      (node (ref "M1") (pin "81") (pinfunction "LCD-VSYNC_81") (pintype "passive"))
    )
    (net (code "33") (name "/LCDS0_VP3") (class "Default")
      (node (ref "J1") (pin "30") (pinfunction "30_30") (pintype "passive"))
      (node (ref "M1") (pin "82") (pinfunction "LCD-HSYNC_82") (pintype "passive"))
    )
    (net (code "34") (name "/LRADC0") (class "Default")
      (node (ref "M1") (pin "115") (pinfunction "LRADC0_115") (pintype "passive"))
      (node (ref "R32") (pin "2") (pinfunction "2_2") (pintype "passive"))
      (node (ref "R35") (pin "1") (pinfunction "1_1") (pintype "passive"))
    )
    (net (code "35") (name "/LVDS0_VN0") (class "Default")
      (node (ref "J1") (pin "23") (pinfunction "23_23") (pintype "passive"))
      (node (ref "M1") (pin "89") (pinfunction "LCD-D19_89") (pintype "passive"))
    )
    (net (code "36") (name "/LVDS0_VN1") (class "Default")
      (node (ref "J1") (pin "25") (pinfunction "25_25") (pintype "passive"))
      (node (ref "M1") (pin "87") (pinfunction "LCD-D21_87") (pintype "passive"))
    )
    (net (code "37") (name "/LVDS0_VN2") (class "Default")
      (node (ref "J1") (pin "27") (pinfunction "27_27") (pintype "passive"))
      (node (ref "M1") (pin "85") (pinfunction "LCD-D23_85") (pintype "passive"))
    )
    (net (code "38") (name "/LVDS0_VNC") (class "Default")
      (node (ref "J1") (pin "31") (pinfunction "31_31") (pintype "passive"))
      (node (ref "M1") (pin "83") (pinfunction "LCD-DE_83") (pintype "passive"))
    )
    (net (code "39") (name "/LVDS0_VP0") (class "Default")
      (node (ref "J1") (pin "22") (pinfunction "22_22") (pintype "passive"))
      (node (ref "M1") (pin "90") (pinfunction "LCD-D18_90") (pintype "passive"))
    )
    (net (code "40") (name "/LVDS0_VP1") (class "Default")
      (node (ref "J1") (pin "24") (pinfunction "24_24") (pintype "passive"))
      (node (ref "M1") (pin "88") (pinfunction "LCD-D20_88") (pintype "passive"))
    )
    (net (code "41") (name "/LVDS0_VP2") (class "Default")
      (node (ref "J1") (pin "26") (pinfunction "26_26") (pintype "passive"))
      (node (ref "M1") (pin "86") (pinfunction "LCD-D22_86") (pintype "passive"))
    )
    (net (code "42") (name "/LVDS0_VPC") (class "Default")
      (node (ref "J1") (pin "28") (pinfunction "28_28") (pintype "passive"))
      (node (ref "M1") (pin "84") (pinfunction "LCD-CLK_84") (pintype "passive"))
    )
    (net (code "43") (name "/MCLK-IN") (class "Default")
      (node (ref "R20") (pin "1") (pinfunction "1_1") (pintype "passive"))
      (node (ref "U6") (pin "30") (pinfunction "TCXO_IN_30") (pintype "passive"))
    )
    (net (code "44") (name "/MIC+") (class "Default")
      (node (ref "C23") (pin "2") (pinfunction "2_2") (pintype "passive"))
      (node (ref "C25") (pin "1") (pinfunction "1_1") (pintype "passive"))
      (node (ref "J6") (pin "1") (pinfunction "1_1") (pintype "passive"))
      (node (ref "M1") (pin "116") (pinfunction "MIC+_116") (pintype "passive"))
    )
    (net (code "45") (name "/MIC-") (class "Default")
      (node (ref "C25") (pin "2") (pinfunction "2_2") (pintype "passive"))
      (node (ref "C27") (pin "1") (pinfunction "1_1") (pintype "passive"))
      (node (ref "J6") (pin "2") (pinfunction "2_2") (pintype "passive"))
      (node (ref "M1") (pin "117") (pinfunction "MIC-_117") (pintype "passive"))
    )
    (net (code "46") (name "/PB6") (class "Default")
      (node (ref "M1") (pin "48") (pinfunction "PB6_48") (pintype "passive"))
    )
    (net (code "47") (name "/PE0_CSI-PCLK") (class "Default")
      (node (ref "J2") (pin "7") (pinfunction "7_7") (pintype "passive"))
      (node (ref "M1") (pin "63") (pinfunction "PE0_CSI-PCLK_63") (pintype "passive"))
    )
    (net (code "48") (name "/PE1_CSI-MCLK") (class "Default")
      (node (ref "J2") (pin "11") (pinfunction "11_11") (pintype "passive"))
      (node (ref "M1") (pin "64") (pinfunction "PE1_CSI-MCLK_64") (pintype "passive"))
    )
    (net (code "49") (name "/PE2_CSI-HSYNC") (class "Default")
      (node (ref "J3") (pin "8") (pinfunction "8_8") (pintype "passive"))
      (node (ref "M1") (pin "65") (pinfunction "PE2_CSI-HSYNC_65") (pintype "passive"))
    )
    (net (code "50") (name "/PE3_CSI-VSYNC") (class "Default")
      (node (ref "J3") (pin "6") (pinfunction "6_6") (pintype "passive"))
      (node (ref "M1") (pin "66") (pinfunction "PE3_CSI-VSYNC_66") (pintype "passive"))
    )
    (net (code "51") (name "/PE4_CSI-D0") (class "Default")
      (node (ref "J2") (pin "5") (pinfunction "5_5") (pintype "passive"))
      (node (ref "M1") (pin "67") (pinfunction "PE4_CSI-D0_67") (pintype "passive"))
    )
    (net (code "52") (name "/PE5_CSI-D1") (class "Default")
      (node (ref "J2") (pin "3") (pinfunction "3_3") (pintype "passive"))
      (node (ref "M1") (pin "68") (pinfunction "PE5_CSI-D1_68") (pintype "passive"))
    )
    (net (code "53") (name "/PE6_CSI-D2") (class "Default")
      (node (ref "J2") (pin "2") (pinfunction "2_2") (pintype "passive"))
      (node (ref "M1") (pin "69") (pinfunction "PE6_CSI-D2_69") (pintype "passive"))
    )
    (net (code "54") (name "/PE7_CSI-D3") (class "Default")
      (node (ref "J2") (pin "4") (pinfunction "4_4") (pintype "passive"))
      (node (ref "M1") (pin "70") (pinfunction "PE7_CSI-D3_70") (pintype "passive"))
    )
    (net (code "55") (name "/PE8_CSI-D4") (class "Default")
      (node (ref "J2") (pin "6") (pinfunction "6_6") (pintype "passive"))
      (node (ref "M1") (pin "71") (pinfunction "PE8_CSI-D4_71") (pintype "passive"))
    )
    (net (code "56") (name "/PE9_CSI-D5") (class "Default")
      (node (ref "J2") (pin "8") (pinfunction "8_8") (pintype "passive"))
      (node (ref "M1") (pin "72") (pinfunction "PE9_CSI-D5_72") (pintype "passive"))
    )
    (net (code "57") (name "/PE10_CSI-D6") (class "Default")
      (node (ref "J2") (pin "10") (pinfunction "10_10") (pintype "passive"))
      (node (ref "M1") (pin "73") (pinfunction "PE10_CSI-D6_73") (pintype "passive"))
    )
    (net (code "58") (name "/PE11_CSI-D7") (class "Default")
      (node (ref "J3") (pin "11") (pinfunction "11_11") (pintype "passive"))
      (node (ref "M1") (pin "74") (pinfunction "PE11_CSI-D7_74") (pintype "passive"))
    )
    (net (code "59") (name "/PE12_CSI-SCK") (class "Default")
      (node (ref "J3") (pin "4") (pinfunction "4_4") (pintype "passive"))
      (node (ref "M1") (pin "75") (pinfunction "PE12_CSI-SCK_75") (pintype "passive"))
    )
    (net (code "60") (name "/PE13_CSI-SDA") (class "Default")
      (node (ref "J3") (pin "2") (pinfunction "2_2") (pintype "passive"))
      (node (ref "M1") (pin "76") (pinfunction "PE13_CSI-SDA_76") (pintype "passive"))
    )
    (net (code "61") (name "/PE16_CSI-RST-F") (class "Default")
      (node (ref "J3") (pin "5") (pinfunction "5_5") (pintype "passive"))
      (node (ref "M1") (pin "79") (pinfunction "PE16_CSI-RST-F_79") (pintype "passive"))
      (node (ref "R12") (pin "2") (pinfunction "2_2") (pintype "passive"))
    )
    (net (code "62") (name "/PE17_CSI-STBY-F") (class "Default")
      (node (ref "J3") (pin "7") (pinfunction "7_7") (pintype "passive"))
      (node (ref "M1") (pin "80") (pinfunction "PE17_CSI-STBY-F_80") (pintype "passive"))
      (node (ref "R9") (pin "1") (pinfunction "1_1") (pintype "passive"))
    )
    (net (code "63") (name "/PH4-SCK1") (class "Default")
      (node (ref "M1") (pin "49") (pinfunction "SCK1/PH4_49") (pintype "passive"))
    )
    (net (code "64") (name "/PH5-SDA1") (class "Default")
      (node (ref "M1") (pin "50") (pinfunction "SDA1/PH5_50") (pintype "passive"))
    )
    (net (code "65") (name "/POWERKEY") (class "Default")
      (node (ref "M1") (pin "14") (pinfunction "POWERKEY_14") (pintype "passive"))
      (node (ref "S1") (pin "2") (pinfunction "2_2") (pintype "passive"))
    )
    (net (code "66") (name "/SDC0-CLK") (class "Default")
      (node (ref "J9") (pin "6") (pinfunction "CLK_6") (pintype "passive"))
      (node (ref "M1") (pin "58") (pinfunction "SDC0-CLK/UART0-TX/PF2_58") (pintype "passive"))
    )
    (net (code "67") (name "/SDC0-CMD") (class "Default")
      (node (ref "J9") (pin "4") (pinfunction "CMD_4") (pintype "power_in"))
      (node (ref "M1") (pin "57") (pinfunction "SDC0-CMD/PF3_57") (pintype "passive"))
    )
    (net (code "68") (name "/SDC0-D0") (class "Default")
      (node (ref "J9") (pin "8") (pinfunction "DAT0_8") (pintype "passive"))
      (node (ref "M1") (pin "53") (pinfunction "SDC0-D0/PF1_53") (pintype "passive"))
    )
    (net (code "69") (name "/SDC0-D1") (class "Default")
      (node (ref "J9") (pin "9") (pinfunction "DAT1_9") (pintype "passive"))
      (node (ref "M1") (pin "54") (pinfunction "SDC0-D1/PF0_54") (pintype "passive"))
    )
    (net (code "70") (name "/SDC0-D2") (class "Default")
      (node (ref "J9") (pin "2") (pinfunction "DAT2_2") (pintype "power_in"))
      (node (ref "M1") (pin "55") (pinfunction "SDC0-D2/PF5_55") (pintype "passive"))
    )
    (net (code "71") (name "/SDC0-D3") (class "Default")
      (node (ref "J9") (pin "3") (pinfunction "DAT3_3") (pintype "power_in"))
      (node (ref "M1") (pin "56") (pinfunction "SDC0-D3/UART0-RX/PF4_56") (pintype "passive"))
    )
    (net (code "72") (name "/SDIO-CLK") (class "Default")
      (node (ref "M1") (pin "42") (pinfunction "WL-SDIO-CLK/PG0_42") (pintype "passive"))
      (node (ref "R40") (pin "2") (pinfunction "2_2") (pintype "passive"))
    )
    (net (code "73") (name "/SDIO-CMD") (class "Default")
      (node (ref "M1") (pin "41") (pinfunction "WL-SDIO-CMD/PG1_41") (pintype "passive"))
      (node (ref "R43") (pin "2") (pinfunction "2_2") (pintype "passive"))
      (node (ref "U6") (pin "16") (pinfunction "SDIO_DATA_CMD_16") (pintype "passive"))
    )
    (net (code "74") (name "/SDIO-D0") (class "Default")
      (node (ref "M1") (pin "43") (pinfunction "WL-SDIO-D0/PG2_43") (pintype "passive"))
      (node (ref "R44") (pin "2") (pinfunction "2_2") (pintype "passive"))
      (node (ref "U6") (pin "18") (pinfunction "SDIO_DATA_0_18") (pintype "passive"))
    )
    (net (code "75") (name "/SDIO-D1") (class "Default")
      (node (ref "M1") (pin "44") (pinfunction "WL-SDIO-D1/PG3_44") (pintype "passive"))
      (node (ref "R45") (pin "2") (pinfunction "2_2") (pintype "passive"))
      (node (ref "U6") (pin "19") (pinfunction "SDIO_DATA_1_19") (pintype "passive"))
    )
    (net (code "76") (name "/SDIO-D2") (class "Default")
      (node (ref "M1") (pin "45") (pinfunction "WL-SDIO-D2/PG4_45") (pintype "passive"))
      (node (ref "R41") (pin "2") (pinfunction "2_2") (pintype "passive"))
      (node (ref "U6") (pin "14") (pinfunction "SDIO_DATA_2_14") (pintype "passive"))
    )
    (net (code "77") (name "/SDIO-D3") (class "Default")
      (node (ref "M1") (pin "46") (pinfunction "WL-SDIO-D3/PG5_46") (pintype "passive"))
      (node (ref "R42") (pin "2") (pinfunction "2_2") (pintype "passive"))
      (node (ref "U6") (pin "15") (pinfunction "SDIO_DATA_3_15") (pintype "passive"))
    )
    (net (code "78") (name "/SPI0-CLK") (class "Default")
      (node (ref "M1") (pin "61") (pinfunction "SPI0-CLK/PC2_61") (pintype "passive"))
    )
    (net (code "79") (name "/SPI0-CS") (class "Default")
      (node (ref "M1") (pin "62") (pinfunction "SPI0-CS/PC3_62") (pintype "passive"))
    )
    (net (code "80") (name "/SPI0-MISO") (class "Default")
      (node (ref "M1") (pin "59") (pinfunction "SPI0-MISO/PC1_59") (pintype "passive"))
    )
    (net (code "81") (name "/SPI0-MOSI") (class "Default")
      (node (ref "M1") (pin "60") (pinfunction "SPI0-MOSI/PC0_60") (pintype "passive"))
    )
    (net (code "82") (name "/T-CARD-DET") (class "Default")
      (node (ref "J9") (pin "10") (pinfunction "CD#_10") (pintype "passive"))
      (node (ref "M1") (pin "52") (pinfunction "T-CARD-DET/PB4_52") (pintype "passive"))
    )
    (net (code "83") (name "/TP-INT") (class "Default")
      (node (ref "J1") (pin "37") (pinfunction "37_37") (pintype "passive"))
      (node (ref "M1") (pin "34") (pinfunction "TP-INT/PB5_34") (pintype "passive"))
    )
    (net (code "84") (name "/TP-RST") (class "Default")
      (node (ref "J1") (pin "40") (pinfunction "40_40") (pintype "passive"))
      (node (ref "M1") (pin "31") (pinfunction "TP-RST/PH1_31") (pintype "passive"))
    )
    (net (code "85") (name "/TP-SCK") (class "Default")
      (node (ref "J1") (pin "39") (pinfunction "39_39") (pintype "passive"))
      (node (ref "M1") (pin "32") (pinfunction "TP-SCK/PH2_32") (pintype "passive"))
      (node (ref "R11") (pin "2") (pinfunction "2_2") (pintype "passive"))
    )
    (net (code "86") (name "/TP-SDA") (class "Default")
      (node (ref "J1") (pin "38") (pinfunction "38_38") (pintype "passive"))
      (node (ref "M1") (pin "33") (pinfunction "TP-SDA/PH3_33") (pintype "passive"))
      (node (ref "R10") (pin "2") (pinfunction "2_2") (pintype "passive"))
    )
    (net (code "87") (name "/Temp") (class "Default")
      (node (ref "C40") (pin "1") (pinfunction "1_1") (pintype "passive"))
      (node (ref "M1") (pin "5") (pinfunction "TS_5") (pintype "passive"))
      (node (ref "R30") (pin "2") (pinfunction "2_2") (pintype "passive"))
      (node (ref "RT4") (pin "1") (pinfunction "1_1") (pintype "passive"))
    )
    (net (code "88") (name "/UART2_CTS") (class "Default")
      (node (ref "M1") (pin "25") (pinfunction "UART2-CTS/PB3_25") (pintype "passive"))
      (node (ref "RT5") (pin "2") (pinfunction "2_2") (pintype "passive"))
    )
    (net (code "89") (name "/USB-DM0") (class "Default")
      (node (ref "D13") (pin "2") (pinfunction "K_2") (pintype "passive"))
      (node (ref "J10") (pin "2") (pinfunction "D-_2") (pintype "passive"))
      (node (ref "M1") (pin "113") (pinfunction "USB-DM0_113") (pintype "passive"))
    )
    (net (code "90") (name "/USB-DM1") (class "Default")
      (node (ref "M1") (pin "111") (pinfunction "USB-DM1_111") (pintype "passive"))
      (node (ref "U1") (pin "25") (pinfunction "DM0_25") (pintype "passive"))
    )
    (net (code "91") (name "/USB-DP0") (class "Default")
      (node (ref "D12") (pin "2") (pinfunction "K_2") (pintype "passive"))
      (node (ref "J10") (pin "3") (pinfunction "D+_3") (pintype "passive"))
      (node (ref "M1") (pin "114") (pinfunction "USB-DP0_114") (pintype "passive"))
    )
    (net (code "92") (name "/USB-DP1") (class "Default")
      (node (ref "M1") (pin "112") (pinfunction "USB-DP1_112") (pintype "passive"))
      (node (ref "U1") (pin "26") (pinfunction "DP0_26") (pintype "passive"))
    )
    (net (code "93") (name "/USB-DRVVBUS") (class "Default")
      (node (ref "M1") (pin "21") (pinfunction "USB-DRVVBUS_21") (pintype "passive"))
      (node (ref "RT1") (pin "2") (pinfunction "2_2") (pintype "passive"))
    )
    (net (code "94") (name "/USB-ID") (class "Default")
      (node (ref "M1") (pin "29") (pinfunction "USB-ID/PH8_29") (pintype "passive"))
      (node (ref "R38") (pin "1") (pinfunction "1_1") (pintype "passive"))
    )
    (net (code "95") (name "/WL-HOST-WAKE") (class "Default")
      (node (ref "M1") (pin "108") (pinfunction "WL-WAKE-AP/PL7_108") (pintype "passive"))
      (node (ref "U6") (pin "13") (pinfunction "WL_HOST_WAKE_13") (pintype "passive"))
    )
    (net (code "96") (name "/WL-REG-ON") (class "Default")
      (node (ref "M1") (pin "107") (pinfunction "WL-PMU-EN/PL6_107") (pintype "passive"))
      (node (ref "R37") (pin "1") (pinfunction "1_1") (pintype "passive"))
      (node (ref "U6") (pin "12") (pinfunction "WL_REG_ON_12") (pintype "passive"))
    )
    (net (code "97") (name "ACIN5V") (class "Default")
      (node (ref "J1") (pin "1") (pinfunction "1_1") (pintype "passive"))
      (node (ref "J1") (pin "2") (pinfunction "2_2") (pintype "passive"))
      (node (ref "J1") (pin "3") (pinfunction "3_3") (pintype "passive"))
      (node (ref "J1") (pin "4") (pinfunction "4_4") (pintype "passive"))
      (node (ref "M1") (pin "15") (pinfunction "ACIN5V_15") (pintype "passive"))
      (node (ref "M1") (pin "16") (pinfunction "ACIN5V_16") (pintype "passive"))
      (node (ref "R14") (pin "1") (pinfunction "1_1") (pintype "passive"))
      (node (ref "R15") (pin "2") (pinfunction "2_2") (pintype "passive"))
    )
    (net (code "98") (name "AVDD-CSI") (class "Default")
      (node (ref "C19") (pin "1") (pinfunction "1_1") (pintype "passive"))
      (node (ref "J3") (pin "3") (pinfunction "3_3") (pintype "passive"))
      (node (ref "M1") (pin "8") (pinfunction "AVDD-CSI_8") (pintype "passive"))
    )
    (net (code "99") (name "DC5V") (class "Default")
      (node (ref "C16") (pin "1") (pinfunction "1_1") (pintype "passive"))
      (node (ref "C17") (pin "2") (pinfunction "2_2") (pintype "passive"))
      (node (ref "C32") (pin "2") (pinfunction "2_2") (pintype "passive"))
      (node (ref "C47") (pin "2") (pinfunction "2_2") (pintype "passive"))
      (node (ref "D9") (pin "2") (pinfunction "K_2") (pintype "passive"))
      (node (ref "R14") (pin "2") (pinfunction "2_2") (pintype "passive"))
      (node (ref "R16") (pin "2") (pinfunction "2_2") (pintype "passive"))
      (node (ref "U2") (pin "5") (pinfunction "OVR_5") (pintype "passive"))
      (node (ref "U5") (pin "5") (pinfunction "IN_5") (pintype "input"))
      (node (ref "U7") (pin "5") (pinfunction "IN_5") (pintype "input"))
    )
    (net (code "100") (name "DOVDD-CSI") (class "Default")
      (node (ref "C11") (pin "1") (pinfunction "1_1") (pintype "passive"))
      (node (ref "C12") (pin "1") (pinfunction "1_1") (pintype "passive"))
      (node (ref "C13") (pin "1") (pinfunction "1_1") (pintype "passive"))
      (node (ref "J3") (pin "10") (pinfunction "10_10") (pintype "passive"))
      (node (ref "M1") (pin "2") (pinfunction "DOVDD-CSI_2") (pintype "passive"))
      (node (ref "R12") (pin "1") (pinfunction "1_1") (pintype "passive"))
      (node (ref "R9") (pin "2") (pinfunction "2_2") (pintype "passive"))
    )
    (net (code "101") (name "DVDD1V8-CSI") (class "Default")
      (node (ref "C18") (pin "1") (pinfunction "1_1") (pintype "passive"))
      (node (ref "J3") (pin "9") (pinfunction "9_9") (pintype "passive"))
      (node (ref "M1") (pin "13") (pinfunction "DVDD1V8-CSI_13") (pintype "passive"))
    )
    (net (code "102") (name "GND") (class "Default")
      (node (ref "ANT1") (pin "2") (pinfunction "2_2") (pintype "passive"))
      (node (ref "ANT1") (pin "3") (pinfunction "3_3") (pintype "passive"))
      (node (ref "C1") (pin "2") (pinfunction "2_2") (pintype "passive"))
      (node (ref "C10") (pin "2") (pinfunction "2_2") (pintype "passive"))
      (node (ref "C11") (pin "2") (pinfunction "2_2") (pintype "passive"))
      (node (ref "C12") (pin "2") (pinfunction "2_2") (pintype "passive"))
      (node (ref "C13") (pin "2") (pinfunction "2_2") (pintype "passive"))
      (node (ref "C14") (pin "2") (pinfunction "2_2") (pintype "passive"))
      (node (ref "C15") (pin "1") (pinfunction "1_1") (pintype "passive"))
      (node (ref "C17") (pin "1") (pinfunction "1_1") (pintype "passive"))
      (node (ref "C18") (pin "2") (pinfunction "2_2") (pintype "passive"))
      (node (ref "C19") (pin "2") (pinfunction "2_2") (pintype "passive"))
      (node (ref "C2") (pin "2") (pinfunction "2_2") (pintype "passive"))
      (node (ref "C20") (pin "1") (pinfunction "1_1") (pintype "passive"))
      (node (ref "C21") (pin "2") (pinfunction "2_2") (pintype "passive"))
      (node (ref "C22") (pin "2") (pinfunction "2_2") (pintype "passive"))
      (node (ref "C23") (pin "1") (pinfunction "1_1") (pintype "passive"))
      (node (ref "C24") (pin "2") (pinfunction "2_2") (pintype "passive"))
      (node (ref "C27") (pin "2") (pinfunction "2_2") (pintype "passive"))
      (node (ref "C29") (pin "2") (pinfunction "2_2") (pintype "passive"))
      (node (ref "C3") (pin "1") (pinfunction "1_1") (pintype "passive"))
      (node (ref "C30") (pin "2") (pinfunction "2_2") (pintype "passive"))
      (node (ref "C31") (pin "2") (pinfunction "2_2") (pintype "passive"))
      (node (ref "C32") (pin "1") (pinfunction "1_1") (pintype "passive"))
      (node (ref "C33") (pin "2") (pinfunction "2_2") (pintype "passive"))
      (node (ref "C34") (pin "2") (pinfunction "2_2") (pintype "passive"))
      (node (ref "C35") (pin "2") (pinfunction "2_2") (pintype "passive"))
      (node (ref "C36") (pin "2") (pinfunction "2_2") (pintype "passive"))
      (node (ref "C37") (pin "1") (pinfunction "1_1") (pintype "passive"))
      (node (ref "C38") (pin "1") (pinfunction "1_1") (pintype "passive"))
      (node (ref "C4") (pin "1") (pinfunction "1_1") (pintype "passive"))
      (node (ref "C40") (pin "2") (pinfunction "2_2") (pintype "passive"))
      (node (ref "C41") (pin "2") (pinfunction "2_2") (pintype "passive"))
      (node (ref "C42") (pin "2") (pinfunction "2_2") (pintype "passive"))
      (node (ref "C43") (pin "2") (pinfunction "2_2") (pintype "passive"))
      (node (ref "C44") (pin "1") (pinfunction "1_1") (pintype "passive"))
      (node (ref "C45") (pin "1") (pinfunction "1_1") (pintype "passive"))
      (node (ref "C46") (pin "1") (pinfunction "1_1") (pintype "passive"))
      (node (ref "C47") (pin "1") (pinfunction "1_1") (pintype "passive"))
      (node (ref "C48") (pin "2") (pinfunction "2_2") (pintype "passive"))
      (node (ref "C49") (pin "2") (pinfunction "2_2") (pintype "passive"))
      (node (ref "C7") (pin "2") (pinfunction "2_2") (pintype "passive"))
      (node (ref "C8") (pin "1") (pinfunction "1_1") (pintype "passive"))
      (node (ref "C9") (pin "2") (pinfunction "2_2") (pintype "passive"))
      (node (ref "D11") (pin "K") (pintype "passive"))
      (node (ref "D12") (pin "1") (pinfunction "A_1") (pintype "passive"))
      (node (ref "D13") (pin "1") (pinfunction "A_1") (pintype "passive"))
      (node (ref "D2") (pin "2") (pinfunction "K_2") (pintype "passive"))
      (node (ref "D3") (pin "2") (pinfunction "K_2") (pintype "passive"))
      (node (ref "D4") (pin "2") (pinfunction "K_2") (pintype "passive"))
      (node (ref "D5") (pin "2") (pinfunction "K_2") (pintype "passive"))
      (node (ref "D6") (pin "2") (pinfunction "K_2") (pintype "passive"))
      (node (ref "D7") (pin "2") (pinfunction "K_2") (pintype "passive"))
      (node (ref "J1") (pin "34") (pinfunction "34_34") (pintype "passive"))
      (node (ref "J1") (pin "41") (pinfunction "41_41") (pintype "passive"))
      (node (ref "J1") (pin "42") (pinfunction "42_42") (pintype "passive"))
      (node (ref "J1") (pin "5") (pinfunction "5_5") (pintype "passive"))
      (node (ref "J1") (pin "6") (pinfunction "6_6") (pintype "passive"))
      (node (ref "J1") (pin "9") (pinfunction "9_9") (pintype "passive"))
      (node (ref "J10") (pin "10") (pinfunction "SHELL_10") (pintype "passive"))
      (node (ref "J10") (pin "5") (pinfunction "GND_5") (pintype "passive"))
      (node (ref "J10") (pin "6") (pinfunction "SHELL_6") (pintype "passive"))
      (node (ref "J10") (pin "7") (pinfunction "SHELL_7") (pintype "passive"))
      (node (ref "J10") (pin "8") (pinfunction "SHELL_8") (pintype "passive"))
      (node (ref "J10") (pin "9") (pinfunction "SHELL_9") (pintype "passive"))
      (node (ref "J2") (pin "1") (pinfunction "1_1") (pintype "passive"))
      (node (ref "J2") (pin "12") (pinfunction "12_12") (pintype "passive"))
      (node (ref "J2") (pin "13") (pinfunction "13_13") (pintype "passive"))
      (node (ref "J2") (pin "14") (pinfunction "14_14") (pintype "passive"))
      (node (ref "J2") (pin "9") (pinfunction "9_9") (pintype "passive"))
      (node (ref "J3") (pin "1") (pinfunction "1_1") (pintype "passive"))
      (node (ref "J3") (pin "12") (pinfunction "12_12") (pintype "passive"))
      (node (ref "J3") (pin "13") (pinfunction "13_13") (pintype "passive"))
      (node (ref "J3") (pin "14") (pinfunction "14_14") (pintype "passive"))
      (node (ref "J4") (pin "10") (pinfunction "GND_10") (pintype "passive"))
      (node (ref "J4") (pin "11") (pinfunction "GND_11") (pintype "passive"))
      (node (ref "J4") (pin "12") (pinfunction "GND_12") (pintype "passive"))
      (node (ref "J4") (pin "4") (pinfunction "GND_4") (pintype "passive"))
      (node (ref "J4") (pin "8") (pinfunction "GND_8") (pintype "passive"))
      (node (ref "J4") (pin "9") (pinfunction "GND_9") (pintype "passive"))
      (node (ref "J5") (pin "4") (pinfunction "GND_4") (pintype "passive"))
      (node (ref "J5") (pin "5") (pinfunction "SHELL_5") (pintype "passive"))
      (node (ref "J5") (pin "6") (pinfunction "SHELL_6") (pintype "passive"))
      (node (ref "J6") (pin "3") (pinfunction "3_3") (pintype "passive"))
      (node (ref "J6") (pin "4") (pinfunction "4_4") (pintype "passive"))
      (node (ref "J7") (pin "3") (pinfunction "3_3") (pintype "passive"))
      (node (ref "J7") (pin "4") (pinfunction "4_4") (pintype "passive"))
      (node (ref "J8") (pin "2") (pinfunction "2_2") (pintype "passive"))
      (node (ref "J9") (pin "11") (pinfunction "GND_11") (pintype "passive"))
      (node (ref "J9") (pin "12") (pinfunction "GND_12") (pintype "passive"))
      (node (ref "J9") (pin "7") (pinfunction "VSS2_7") (pintype "passive"))
      (node (ref "M1") (pin "103") (pinfunction "GND_103") (pintype "passive"))
      (node (ref "M1") (pin "121") (pinfunction "GND_121") (pintype "passive"))
      (node (ref "M1") (pin "122") (pinfunction "GND_122") (pintype "passive"))
      (node (ref "M1") (pin "123") (pinfunction "GND_123") (pintype "passive"))
      (node (ref "M1") (pin "124") (pinfunction "GND_124") (pintype "passive"))
      (node (ref "M1") (pin "40") (pinfunction "GND_40") (pintype "passive"))
      (node (ref "M1") (pin "51") (pinfunction "GND_51") (pintype "passive"))
      (node (ref "M1") (pin "9") (pinfunction "GND_9") (pintype "passive"))
      (node (ref "R1") (pin "2") (pinfunction "2_2") (pintype "passive"))
      (node (ref "R17") (pin "1") (pinfunction "1_1") (pintype "passive"))
      (node (ref "R18") (pin "1") (pinfunction "1_1") (pintype "passive"))
      (node (ref "R27") (pin "2") (pinfunction "2_2") (pintype "passive"))
      (node (ref "R30") (pin "1") (pinfunction "1_1") (pintype "passive"))
      (node (ref "R31") (pin "2") (pinfunction "2_2") (pintype "passive"))
      (node (ref "R37") (pin "2") (pinfunction "2_2") (pintype "passive"))
      (node (ref "R8") (pin "1") (pinfunction "1_1") (pintype "passive"))
      (node (ref "RT2") (pin "1") (pinfunction "1_1") (pintype "passive"))
      (node (ref "RT3") (pin "1") (pinfunction "1_1") (pintype "passive"))
      (node (ref "RT6") (pin "1") (pinfunction "1_1") (pintype "passive"))
      (node (ref "RT7") (pin "1") (pinfunction "1_1") (pintype "passive"))
      (node (ref "S1") (pin "1") (pinfunction "1_1") (pintype "passive"))
      (node (ref "U1") (pin "15") (pinfunction "GND_15") (pintype "passive"))
      (node (ref "U2") (pin "2") (pinfunction "GND_2") (pintype "power_in"))
      (node (ref "U3") (pin "2") (pinfunction "GND_2") (pintype "passive"))
      (node (ref "U4") (pin "8") (pinfunction "GND_8") (pintype "passive"))
      (node (ref "U5") (pin "2") (pinfunction "GND_2") (pintype "power_in"))
      (node (ref "U6") (pin "1") (pinfunction "GND_1") (pintype "passive"))
      (node (ref "U6") (pin "20") (pinfunction "GND_20") (pintype "passive"))
      (node (ref "U6") (pin "3") (pinfunction "GND_3") (pintype "passive"))
      (node (ref "U6") (pin "31") (pinfunction "GND_31") (pintype "passive"))
      (node (ref "U6") (pin "33") (pinfunction "GND_33") (pintype "passive"))
      (node (ref "U6") (pin "36") (pinfunction "GND_36") (pintype "passive"))
      (node (ref "U7") (pin "2") (pinfunction "GND_2") (pintype "power_in"))
      (node (ref "Y1") (pin "2") (pinfunction "GND_2") (pintype "passive"))
      (node (ref "Y1") (pin "4") (pinfunction "GND_4") (pintype "passive"))
      (node (ref "Y2") (pin "2") (pinfunction "GND_2") (pintype "passive"))
      (node (ref "Y2") (pin "4") (pinfunction "GND_4") (pintype "passive"))
    )
    (net (code "103") (name "HOST2_5V") (class "Default")
      (node (ref "C10") (pin "1") (pinfunction "1_1") (pintype "passive"))
      (node (ref "C29") (pin "1") (pinfunction "1_1") (pintype "passive"))
      (node (ref "C33") (pin "1") (pinfunction "1_1") (pintype "passive"))
      (node (ref "C34") (pin "1") (pinfunction "1_1") (pintype "passive"))
      (node (ref "C35") (pin "1") (pinfunction "1_1") (pintype "passive"))
      (node (ref "C42") (pin "1") (pinfunction "1_1") (pintype "passive"))
      (node (ref "C43") (pin "1") (pinfunction "1_1") (pintype "passive"))
      (node (ref "C44") (pin "2") (pinfunction "2_2") (pintype "passive"))
      (node (ref "C48") (pin "1") (pinfunction "1_1") (pintype "passive"))
      (node (ref "C8") (pin "2") (pinfunction "2_2") (pintype "passive"))
      (node (ref "C9") (pin "1") (pinfunction "1_1") (pintype "passive"))
      (node (ref "J10") (pin "1") (pinfunction "VCC_1") (pintype "passive"))
      (node (ref "J4") (pin "1") (pinfunction "VCC_1") (pintype "passive"))
      (node (ref "J4") (pin "5") (pinfunction "VCC_5") (pintype "passive"))
      (node (ref "J5") (pin "1") (pinfunction "VCC_1") (pintype "passive"))
      (node (ref "M1") (pin "12") (pinfunction "USBVBUS_12") (pintype "passive"))
      (node (ref "R15") (pin "1") (pinfunction "1_1") (pintype "passive"))
      (node (ref "U4") (pin "5") (pinfunction "VDD_5") (pintype "passive"))
      (node (ref "U5") (pin "1") (pinfunction "VOUT1_1") (pintype "output"))
      (node (ref "U7") (pin "1") (pinfunction "VOUT1_1") (pintype "output"))
    )
    (net (code "104") (name "Net-(ANT1-W)") (class "Default")
      (node (ref "ANT1") (pin "1") (pinfunction "W_1") (pintype "passive"))
      (node (ref "C37") (pin "2") (pinfunction "2_2") (pintype "passive"))
      (node (ref "C39") (pin "2") (pinfunction "2_2") (pintype "passive"))
    )
    (net (code "105") (name "Net-(C1-Pad1)") (class "Default")
      (node (ref "C1") (pin "1") (pinfunction "1_1") (pintype "passive"))
      (node (ref "C2") (pin "1") (pinfunction "1_1") (pintype "passive"))
      (node (ref "L1") (pin "2") (pinfunction "2_2") (pintype "passive"))
      (node (ref "U1") (pin "1") (pinfunction "AVDD_1") (pintype "passive"))
      (node (ref "U1") (pin "10") (pinfunction "AVDD_10") (pintype "passive"))
      (node (ref "U1") (pin "5") (pinfunction "AVDD_5") (pintype "passive"))
    )
    (net (code "106") (name "Net-(C24-Pad1)") (class "Default")
      (node (ref "C24") (pin "1") (pinfunction "1_1") (pintype "passive"))
      (node (ref "J7") (pin "1") (pinfunction "1_1") (pintype "passive"))
      (node (ref "L3") (pin "1") (pinfunction "1_1") (pintype "passive"))
    )
    (net (code "107") (name "Net-(C26-Pad2)") (class "Default")
      (node (ref "C26") (pin "2") (pinfunction "2_2") (pintype "passive"))
      (node (ref "R23") (pin "1") (pinfunction "1_1") (pintype "passive"))
    )
    (net (code "108") (name "Net-(C28-Pad2)") (class "Default")
      (node (ref "C28") (pin "2") (pinfunction "2_2") (pintype "passive"))
      (node (ref "R24") (pin "1") (pinfunction "1_1") (pintype "passive"))
    )
    (net (code "109") (name "Net-(C30-Pad1)") (class "Default")
      (node (ref "C30") (pin "1") (pinfunction "1_1") (pintype "passive"))
      (node (ref "J7") (pin "2") (pinfunction "2_2") (pintype "passive"))
      (node (ref "L4") (pin "1") (pinfunction "1_1") (pintype "passive"))
    )
    (net (code "110") (name "Net-(D9-A)") (class "Default")
      (node (ref "D9") (pin "1") (pinfunction "A_1") (pintype "passive"))
      (node (ref "L2") (pin "2") (pinfunction "2_2") (pintype "passive"))
      (node (ref "U2") (pin "1") (pinfunction "LX_1") (pintype "passive"))
    )
    (net (code "111") (name "Net-(D10-PadK)") (class "Default")
      (node (ref "D10") (pin "K") (pintype "passive"))
      (node (ref "R28") (pin "1") (pinfunction "1_1") (pintype "passive"))
    )
    (net (code "112") (name "Net-(D11-PadA)") (class "Default")
      (node (ref "D11") (pin "A") (pintype "passive"))
      (node (ref "R33") (pin "1") (pinfunction "1_1") (pintype "passive"))
    )
    (net (code "113") (name "Net-(D19-Pad2)") (class "Default")
      (node (ref "D19") (pin "2") (pinfunction "2_2") (pintype "passive"))
      (node (ref "R5") (pin "1") (pinfunction "1_1") (pintype "passive"))
    )
    (net (code "114") (name "Net-(J9-Voice_Key)") (class "Default")
      (node (ref "J9") (pin "1") (pinfunction "Voice_Key_1") (pintype "passive"))
      (node (ref "R35") (pin "2") (pinfunction "2_2") (pintype "passive"))
    )
    (net (code "115") (name "Net-(J10-ID)") (class "Default")
      (node (ref "J10") (pin "4") (pinfunction "ID_4") (pintype "passive"))
      (node (ref "R38") (pin "2") (pinfunction "2_2") (pintype "passive"))
      (node (ref "R39") (pin "1") (pinfunction "1_1") (pintype "passive"))
    )
    (net (code "116") (name "Net-(M1-PA-SHDN{slash}PH9)") (class "Default")
      (node (ref "M1") (pin "39") (pinfunction "PA-SHDN/PH9_39") (pintype "passive"))
      (node (ref "R13") (pin "2") (pinfunction "2_2") (pintype "passive"))
    )
    (net (code "117") (name "Net-(U1-OVCUR1)") (class "Default")
      (node (ref "R2") (pin "2") (pinfunction "2_2") (pintype "passive"))
      (node (ref "U1") (pin "21") (pinfunction "OVCUR1_21") (pintype "passive"))
    )
    (net (code "118") (name "Net-(U1-PGANG)") (class "Default")
      (node (ref "R4") (pin "2") (pinfunction "2_2") (pintype "passive"))
      (node (ref "R5") (pin "2") (pinfunction "2_2") (pintype "passive"))
      (node (ref "U1") (pin "18") (pinfunction "PGANG_18") (pintype "passive"))
    )
    (net (code "119") (name "Net-(U1-PSELF)") (class "Default")
      (node (ref "R6") (pin "2") (pinfunction "2_2") (pintype "passive"))
      (node (ref "U1") (pin "17") (pinfunction "PSELF_17") (pintype "passive"))
    )
    (net (code "120") (name "Net-(U1-RESET)") (class "Default")
      (node (ref "C7") (pin "1") (pinfunction "1_1") (pintype "passive"))
      (node (ref "R7") (pin "1") (pinfunction "1_1") (pintype "passive"))
      (node (ref "R8") (pin "2") (pinfunction "2_2") (pintype "passive"))
      (node (ref "U1") (pin "13") (pinfunction "RESET_13") (pintype "passive"))
    )
    (net (code "121") (name "Net-(U1-RREF)") (class "Default")
      (node (ref "R1") (pin "1") (pinfunction "1_1") (pintype "passive"))
      (node (ref "U1") (pin "4") (pinfunction "RREF_4") (pintype "passive"))
    )
    (net (code "122") (name "Net-(U1-X1)") (class "Default")
      (node (ref "C5") (pin "2") (pinfunction "2_2") (pintype "passive"))
      (node (ref "R3") (pin "2") (pinfunction "2_2") (pintype "passive"))
      (node (ref "U1") (pin "6") (pinfunction "X1_6") (pintype "passive"))
    )
    (net (code "123") (name "Net-(U1-X2)") (class "Default")
      (node (ref "C6") (pin "2") (pinfunction "2_2") (pintype "passive"))
      (node (ref "R3") (pin "1") (pinfunction "1_1") (pintype "passive"))
      (node (ref "U1") (pin "7") (pinfunction "X2_7") (pintype "passive"))
    )
    (net (code "124") (name "Net-(U2-FB)") (class "Default")
      (node (ref "C16") (pin "2") (pinfunction "2_2") (pintype "passive"))
      (node (ref "R16") (pin "1") (pinfunction "1_1") (pintype "passive"))
      (node (ref "R18") (pin "2") (pinfunction "2_2") (pintype "passive"))
      (node (ref "U2") (pin "3") (pinfunction "FB_3") (pintype "passive"))
    )
    (net (code "125") (name "Net-(U2-VDD)") (class "Default")
      (node (ref "D8") (pin "3") (pinfunction "3_3") (pintype "passive"))
      (node (ref "L2") (pin "1") (pinfunction "1_1") (pintype "passive"))
      (node (ref "U2") (pin "6") (pinfunction "VDD_6") (pintype "power_in"))
    )
    (net (code "126") (name "Net-(U3-IN_A1)") (class "Default")
      (node (ref "R19") (pin "1") (pinfunction "1_1") (pintype "passive"))
      (node (ref "R22") (pin "2") (pinfunction "2_2") (pintype "passive"))
      (node (ref "U3") (pin "1") (pinfunction "IN_A1_1") (pintype "passive"))
      (node (ref "U3") (pin "4") (pinfunction "OUT_Y2_4") (pintype "passive"))
    )
    (net (code "127") (name "Net-(U3-IN_A2)") (class "Default")
      (node (ref "C31") (pin "1") (pinfunction "1_1") (pintype "passive"))
      (node (ref "R22") (pin "1") (pinfunction "1_1") (pintype "passive"))
      (node (ref "U3") (pin "3") (pinfunction "IN_A2_3") (pintype "passive"))
      (node (ref "Y2") (pin "3") (pinfunction "XO_3") (pintype "passive"))
    )
    (net (code "128") (name "Net-(U3-OUT_Y1)") (class "Default")
      (node (ref "R20") (pin "2") (pinfunction "2_2") (pintype "passive"))
      (node (ref "U3") (pin "6") (pinfunction "OUT_Y1_6") (pintype "passive"))
    )
    (net (code "129") (name "Net-(U3-VCC)") (class "Default")
      (node (ref "R21") (pin "2") (pinfunction "2_2") (pintype "passive"))
      (node (ref "U3") (pin "5") (pinfunction "VCC_5") (pintype "passive"))
    )
    (net (code "130") (name "Net-(U4-IN+)") (class "Default")
      (node (ref "R23") (pin "2") (pinfunction "2_2") (pintype "passive"))
      (node (ref "U4") (pin "3") (pinfunction "IN+_3") (pintype "passive"))
    )
    (net (code "131") (name "Net-(U4-IN-)") (class "Default")
      (node (ref "R24") (pin "2") (pinfunction "2_2") (pintype "passive"))
      (node (ref "U4") (pin "4") (pinfunction "IN-_4") (pintype "passive"))
    )
    (net (code "132") (name "Net-(U4-OUT+)") (class "Default")
      (node (ref "L3") (pin "2") (pinfunction "2_2") (pintype "passive"))
      (node (ref "U4") (pin "7") (pinfunction "OUT+_7") (pintype "passive"))
    )
    (net (code "133") (name "Net-(U4-OUT-)") (class "Default")
      (node (ref "L4") (pin "2") (pinfunction "2_2") (pintype "passive"))
      (node (ref "U4") (pin "6") (pinfunction "OUT-_6") (pintype "passive"))
    )
    (net (code "134") (name "Net-(U5-EN)") (class "Default")
      (node (ref "RT1") (pin "1") (pinfunction "1_1") (pintype "passive"))
      (node (ref "RT2") (pin "2") (pinfunction "2_2") (pintype "passive"))
      (node (ref "U5") (pin "4") (pinfunction "EN_4") (pintype "passive"))
    )
    (net (code "135") (name "Net-(U5-FLAG)") (class "Default")
      (node (ref "RT3") (pin "2") (pinfunction "2_2") (pintype "passive"))
      (node (ref "U5") (pin "3") (pinfunction "FLAG_3") (pintype "passive"))
    )
    (net (code "136") (name "Net-(U6-LPO)") (class "Default")
      (node (ref "R34") (pin "1") (pinfunction "1_1") (pintype "passive"))
      (node (ref "U6") (pin "24") (pinfunction "LPO_24") (pintype "passive"))
    )
    (net (code "137") (name "Net-(U6-SDIO_DATA_CLK)") (class "Default")
      (node (ref "R40") (pin "1") (pinfunction "1_1") (pintype "passive"))
      (node (ref "U6") (pin "17") (pinfunction "SDIO_DATA_CLK_17") (pintype "passive"))
    )
    (net (code "138") (name "Net-(U6-VIN_LDO)") (class "Default")
      (node (ref "C46") (pin "2") (pinfunction "2_2") (pintype "passive"))
      (node (ref "L5") (pin "2") (pinfunction "2_2") (pintype "passive"))
      (node (ref "U6") (pin "23") (pinfunction "VIN_LDO_23") (pintype "passive"))
    )
    (net (code "139") (name "Net-(U6-VIN_LDO_OUT)") (class "Default")
      (node (ref "L5") (pin "1") (pinfunction "1_1") (pintype "passive"))
      (node (ref "U6") (pin "21") (pinfunction "VIN_LDO_OUT_21") (pintype "passive"))
    )
    (net (code "140") (name "Net-(U6-WL_BT_ANT)") (class "Default")
      (node (ref "C38") (pin "2") (pinfunction "2_2") (pintype "passive"))
      (node (ref "C39") (pin "1") (pinfunction "1_1") (pintype "passive"))
      (node (ref "U6") (pin "2") (pinfunction "WL_BT_ANT_2") (pintype "passive"))
    )
    (net (code "141") (name "Net-(U6-WL_VDD_TCXO)") (class "Default")
      (node (ref "R29") (pin "1") (pinfunction "1_1") (pintype "passive"))
      (node (ref "U6") (pin "29") (pinfunction "WL_VDD_TCXO_29") (pintype "passive"))
    )
    (net (code "142") (name "Net-(U7-EN)") (class "Default")
      (node (ref "RT5") (pin "1") (pinfunction "1_1") (pintype "passive"))
      (node (ref "RT6") (pin "2") (pinfunction "2_2") (pintype "passive"))
      (node (ref "U7") (pin "4") (pinfunction "EN_4") (pintype "passive"))
    )
    (net (code "143") (name "Net-(U7-FLAG)") (class "Default")
      (node (ref "RT7") (pin "2") (pinfunction "2_2") (pintype "passive"))
      (node (ref "U7") (pin "3") (pinfunction "FLAG_3") (pintype "passive"))
    )
    (net (code "144") (name "Net-(Y1-XI)") (class "Default")
      (node (ref "C6") (pin "1") (pinfunction "1_1") (pintype "passive"))
      (node (ref "Y1") (pin "1") (pinfunction "XI_1") (pintype "passive"))
    )
    (net (code "145") (name "Net-(Y1-XO)") (class "Default")
      (node (ref "C5") (pin "1") (pinfunction "1_1") (pintype "passive"))
      (node (ref "Y1") (pin "3") (pinfunction "XO_3") (pintype "passive"))
    )
    (net (code "146") (name "Net-(Y2-XI)") (class "Default")
      (node (ref "C22") (pin "1") (pinfunction "1_1") (pintype "passive"))
      (node (ref "R19") (pin "2") (pinfunction "2_2") (pintype "passive"))
      (node (ref "Y2") (pin "1") (pinfunction "XI_1") (pintype "passive"))
    )
    (net (code "147") (name "PS") (class "Default")
      (node (ref "C14") (pin "1") (pinfunction "1_1") (pintype "passive"))
      (node (ref "C15") (pin "2") (pinfunction "2_2") (pintype "passive"))
      (node (ref "D10") (pin "A") (pintype "passive"))
      (node (ref "D8") (pin "1") (pinfunction "1_1") (pintype "passive"))
      (node (ref "M1") (pin "10") (pinfunction "PS_10") (pintype "passive"))
      (node (ref "M1") (pin "11") (pinfunction "PS_11") (pintype "passive"))
    )
    (net (code "148") (name "VBAT") (class "Default")
      (node (ref "C20") (pin "2") (pinfunction "2_2") (pintype "passive"))
      (node (ref "C21") (pin "1") (pinfunction "1_1") (pintype "passive"))
      (node (ref "C36") (pin "1") (pinfunction "1_1") (pintype "passive"))
      (node (ref "D8") (pin "2") (pinfunction "2_2") (pintype "passive"))
      (node (ref "J8") (pin "1") (pinfunction "1_1") (pintype "passive"))
      (node (ref "M1") (pin "19") (pinfunction "VBAT_19") (pintype "passive"))
      (node (ref "M1") (pin "20") (pinfunction "VBAT_20") (pintype "passive"))
    )
    (net (code "149") (name "VCC-3V0") (class "Default")
      (node (ref "C3") (pin "2") (pinfunction "2_2") (pintype "passive"))
      (node (ref "C4") (pin "2") (pinfunction "2_2") (pintype "passive"))
      (node (ref "D19") (pin "1") (pinfunction "1_1") (pintype "passive"))
      (node (ref "J9") (pin "5") (pinfunction "VDD_5") (pintype "passive"))
      (node (ref "L1") (pin "1") (pinfunction "1_1") (pintype "passive"))
      (node (ref "M1") (pin "1") (pinfunction "VCC-3V0_1") (pintype "passive"))
      (node (ref "R13") (pin "1") (pinfunction "1_1") (pintype "passive"))
      (node (ref "R17") (pin "2") (pinfunction "2_2") (pintype "passive"))
      (node (ref "R2") (pin "1") (pinfunction "1_1") (pintype "passive"))
      (node (ref "R32") (pin "1") (pinfunction "1_1") (pintype "passive"))
      (node (ref "R33") (pin "2") (pinfunction "2_2") (pintype "passive"))
      (node (ref "R39") (pin "2") (pinfunction "2_2") (pintype "passive"))
      (node (ref "R4") (pin "1") (pinfunction "1_1") (pintype "passive"))
      (node (ref "R6") (pin "1") (pinfunction "1_1") (pintype "passive"))
      (node (ref "R7") (pin "2") (pinfunction "2_2") (pintype "passive"))
      (node (ref "U1") (pin "16") (pinfunction "DVDD_16") (pintype "passive"))
      (node (ref "U1") (pin "24") (pinfunction "V33_24") (pintype "passive"))
      (node (ref "U2") (pin "4") (pinfunction "EN_4") (pintype "passive"))
      (node (ref "U4") (pin "1") (pinfunction "SD_1") (pintype "passive"))
      (node (ref "U4") (pin "2") (pinfunction "ABD_2") (pintype "passive"))
    )
    (net (code "150") (name "VCC-CTP") (class "Default")
      (node (ref "J1") (pin "35") (pinfunction "35_35") (pintype "passive"))
      (node (ref "J1") (pin "36") (pinfunction "36_36") (pintype "passive"))
      (node (ref "M1") (pin "6") (pinfunction "VCC-CTP_6") (pintype "passive"))
      (node (ref "R10") (pin "1") (pinfunction "1_1") (pintype "passive"))
      (node (ref "R11") (pin "1") (pinfunction "1_1") (pintype "passive"))
    )
    (net (code "151") (name "VCC-LCD") (class "Default")
      (node (ref "J1") (pin "7") (pinfunction "7_7") (pintype "passive"))
      (node (ref "J1") (pin "8") (pinfunction "8_8") (pintype "passive"))
      (node (ref "M1") (pin "4") (pinfunction "VCC-LCD_4") (pintype "passive"))
      (node (ref "RT4") (pin "2") (pinfunction "2_2") (pintype "passive"))
    )
    (net (code "152") (name "VCC-WIFI") (class "Default")
      (node (ref "C41") (pin "1") (pinfunction "1_1") (pintype "passive"))
      (node (ref "C45") (pin "2") (pinfunction "2_2") (pintype "passive"))
      (node (ref "C49") (pin "1") (pinfunction "1_1") (pintype "passive"))
      (node (ref "M1") (pin "3") (pinfunction "VCC-IO-WIFI_3") (pintype "passive"))
      (node (ref "R21") (pin "1") (pinfunction "1_1") (pintype "passive"))
      (node (ref "R25") (pin "1") (pinfunction "1_1") (pintype "passive"))
      (node (ref "R26") (pin "1") (pinfunction "1_1") (pintype "passive"))
      (node (ref "R29") (pin "2") (pinfunction "2_2") (pintype "passive"))
      (node (ref "R36") (pin "1") (pinfunction "1_1") (pintype "passive"))
      (node (ref "R41") (pin "1") (pinfunction "1_1") (pintype "passive"))
      (node (ref "R42") (pin "1") (pinfunction "1_1") (pintype "passive"))
      (node (ref "R43") (pin "1") (pinfunction "1_1") (pintype "passive"))
      (node (ref "R44") (pin "1") (pinfunction "1_1") (pintype "passive"))
      (node (ref "R45") (pin "1") (pinfunction "1_1") (pintype "passive"))
      (node (ref "U6") (pin "22") (pinfunction "VDDIO_22") (pintype "passive"))
      (node (ref "U6") (pin "9") (pinfunction "VBAT_9") (pintype "passive"))
    )
    (net (code "153") (name "unconnected-(M1-NC-Pad125)") (class "Default")
      (node (ref "M1") (pin "125") (pinfunction "NC_125") (pintype "passive"))
    )
    (net (code "154") (name "unconnected-(M1-NC-Pad126)") (class "Default")
      (node (ref "M1") (pin "126") (pinfunction "NC_126") (pintype "passive"))
    )
    (net (code "155") (name "unconnected-(M1-PE14_CSI-RST-R-Pad77)") (class "Default")
      (node (ref "M1") (pin "77") (pinfunction "PE14_CSI-RST-R_77") (pintype "passive"))
    )
    (net (code "156") (name "unconnected-(M1-PE15_CSI-STBY-R-Pad78)") (class "Default")
      (node (ref "M1") (pin "78") (pinfunction "PE15_CSI-STBY-R_78") (pintype "passive"))
    )
    (net (code "157") (name "unconnected-(M1-PL11-Pad104)") (class "Default")
      (node (ref "M1") (pin "104") (pinfunction "PL11_104") (pintype "passive"))
    )
    (net (code "158") (name "unconnected-(M1-RESET-N-Pad22)") (class "Default")
      (node (ref "M1") (pin "22") (pinfunction "RESET-N_22") (pintype "passive"))
    )
    (net (code "159") (name "unconnected-(M1-UART2-RTS{slash}PB2-Pad26)") (class "Default")
      (node (ref "M1") (pin "26") (pinfunction "UART2-RTS/PB2_26") (pintype "passive"))
    )
    (net (code "160") (name "unconnected-(M1-UART2-RX{slash}PB1-Pad23)") (class "Default")
      (node (ref "M1") (pin "23") (pinfunction "UART2-RX/PB1_23") (pintype "passive"))
    )
    (net (code "161") (name "unconnected-(M1-UART2-TX{slash}PB0-Pad24)") (class "Default")
      (node (ref "M1") (pin "24") (pinfunction "UART2-TX/PB0_24") (pintype "passive"))
    )
    (net (code "162") (name "unconnected-(M1-UART3-RX{slash}PH7-Pad27)") (class "Default")
      (node (ref "M1") (pin "27") (pinfunction "UART3-RX/PH7_27") (pintype "passive"))
    )
    (net (code "163") (name "unconnected-(M1-UART3-TX{slash}PH6-Pad28)") (class "Default")
      (node (ref "M1") (pin "28") (pinfunction "UART3-TX/PH6_28") (pintype "passive"))
    )
    (net (code "164") (name "unconnected-(M1-VBAT-EXT-Pad17)") (class "Default")
      (node (ref "M1") (pin "17") (pinfunction "VBAT-EXT_17") (pintype "passive"))
    )
    (net (code "165") (name "unconnected-(M1-VBAT-EXT-Pad18)") (class "Default")
      (node (ref "M1") (pin "18") (pinfunction "VBAT-EXT_18") (pintype "passive"))
    )
    (net (code "166") (name "unconnected-(M1-VCC-RTC-Pad7)") (class "Default")
      (node (ref "M1") (pin "7") (pinfunction "VCC-RTC_7") (pintype "passive"))
    )
    (net (code "167") (name "unconnected-(U1-DM3-Pad8)") (class "Default")
      (node (ref "U1") (pin "8") (pinfunction "DM3_8") (pintype "passive+no_connect"))
    )
    (net (code "168") (name "unconnected-(U1-DP3-Pad9)") (class "Default")
      (node (ref "U1") (pin "9") (pinfunction "DP3_9") (pintype "passive+no_connect"))
    )
    (net (code "169") (name "unconnected-(U1-OVCUR2-Pad19)") (class "Default")
      (node (ref "U1") (pin "19") (pinfunction "OVCUR2_19") (pintype "passive+no_connect"))
    )
    (net (code "170") (name "unconnected-(U1-PWREN1-Pad22)") (class "Default")
      (node (ref "U1") (pin "22") (pinfunction "PWREN1_22") (pintype "passive+no_connect"))
    )
    (net (code "171") (name "unconnected-(U1-PWREN2-Pad20)") (class "Default")
      (node (ref "U1") (pin "20") (pinfunction "PWREN2_20") (pintype "passive+no_connect"))
    )
    (net (code "172") (name "unconnected-(U1-TEST{slash}SCL-Pad14)") (class "Default")
      (node (ref "U1") (pin "14") (pinfunction "TEST/SCL_14") (pintype "passive+no_connect"))
    )
    (net (code "173") (name "unconnected-(U1-V5-Pad23)") (class "Default")
      (node (ref "U1") (pin "23") (pinfunction "V5_23") (pintype "passive+no_connect"))
    )
    (net (code "174") (name "unconnected-(U6-BT_XTAL_IN-Pad37)") (class "Default")
      (node (ref "U6") (pin "37") (pinfunction "BT_XTAL_IN_37") (pintype "passive"))
    )
    (net (code "175") (name "unconnected-(U6-BT_XTAL_OUT-Pad38)") (class "Default")
      (node (ref "U6") (pin "38") (pinfunction "BT_XTAL_OUT_38") (pintype "passive"))
    )
    (net (code "176") (name "unconnected-(U6-NC-Pad4)") (class "Default")
      (node (ref "U6") (pin "4") (pinfunction "NC_4") (pintype "passive"))
    )
    (net (code "177") (name "unconnected-(U6-NC-Pad5)") (class "Default")
      (node (ref "U6") (pin "5") (pinfunction "NC_5") (pintype "passive"))
    )
    (net (code "178") (name "unconnected-(U6-NC-Pad8)") (class "Default")
      (node (ref "U6") (pin "8") (pinfunction "NC_8") (pintype "passive"))
    )
    (net (code "179") (name "unconnected-(U6-NC-Pad10)") (class "Default")
      (node (ref "U6") (pin "10") (pinfunction "NC_10") (pintype "passive"))
    )
    (net (code "180") (name "unconnected-(U6-NC-Pad11)") (class "Default")
      (node (ref "U6") (pin "11") (pinfunction "NC_11") (pintype "passive"))
    )
    (net (code "181") (name "unconnected-(U6-NC-Pad32)") (class "Default")
      (node (ref "U6") (pin "32") (pinfunction "NC_32") (pintype "passive"))
    )
    (net (code "182") (name "unconnected-(U6-NC-Pad35)") (class "Default")
      (node (ref "U6") (pin "35") (pinfunction "NC_35") (pintype "passive"))
    )
    (net (code "183") (name "unconnected-(U6-NC-Pad39)") (class "Default")
      (node (ref "U6") (pin "39") (pinfunction "NC_39") (pintype "passive"))
    )
    (net (code "184") (name "unconnected-(U6-NC-Pad40)") (class "Default")
      (node (ref "U6") (pin "40") (pinfunction "NC_40") (pintype "passive"))
    )
    (net (code "185") (name "unconnected-(U6-NC-Pad45)") (class "Default")
      (node (ref "U6") (pin "45") (pinfunction "NC_45") (pintype "passive"))
    )
    (net (code "186") (name "unconnected-(U6-NC-Pad46)") (class "Default")
      (node (ref "U6") (pin "46") (pinfunction "NC_46") (pintype "passive"))
    )
    (net (code "187") (name "unconnected-(U6-NC-Pad47)") (class "Default")
      (node (ref "U6") (pin "47") (pinfunction "NC_47") (pintype "passive"))
    )
    (net (code "188") (name "unconnected-(U6-PCM_CLK-Pad26)") (class "Default")
      (node (ref "U6") (pin "26") (pinfunction "PCM_CLK_26") (pintype "passive"))
    )
    (net (code "189") (name "unconnected-(U6-PCM_IN-Pad27)") (class "Default")
      (node (ref "U6") (pin "27") (pinfunction "PCM_IN_27") (pintype "passive"))
    )
    (net (code "190") (name "unconnected-(U6-PCM_OUT-Pad25)") (class "Default")
      (node (ref "U6") (pin "25") (pinfunction "PCM_OUT_25") (pintype "passive"))
    )
    (net (code "191") (name "unconnected-(U6-PCM_SYNC-Pad28)") (class "Default")
      (node (ref "U6") (pin "28") (pinfunction "PCM_SYNC_28") (pintype "passive"))
    )
  )
)
